# ccnor_stm32_v22-sync.net
KiCad netlist of a schematic drawn in EAGLE
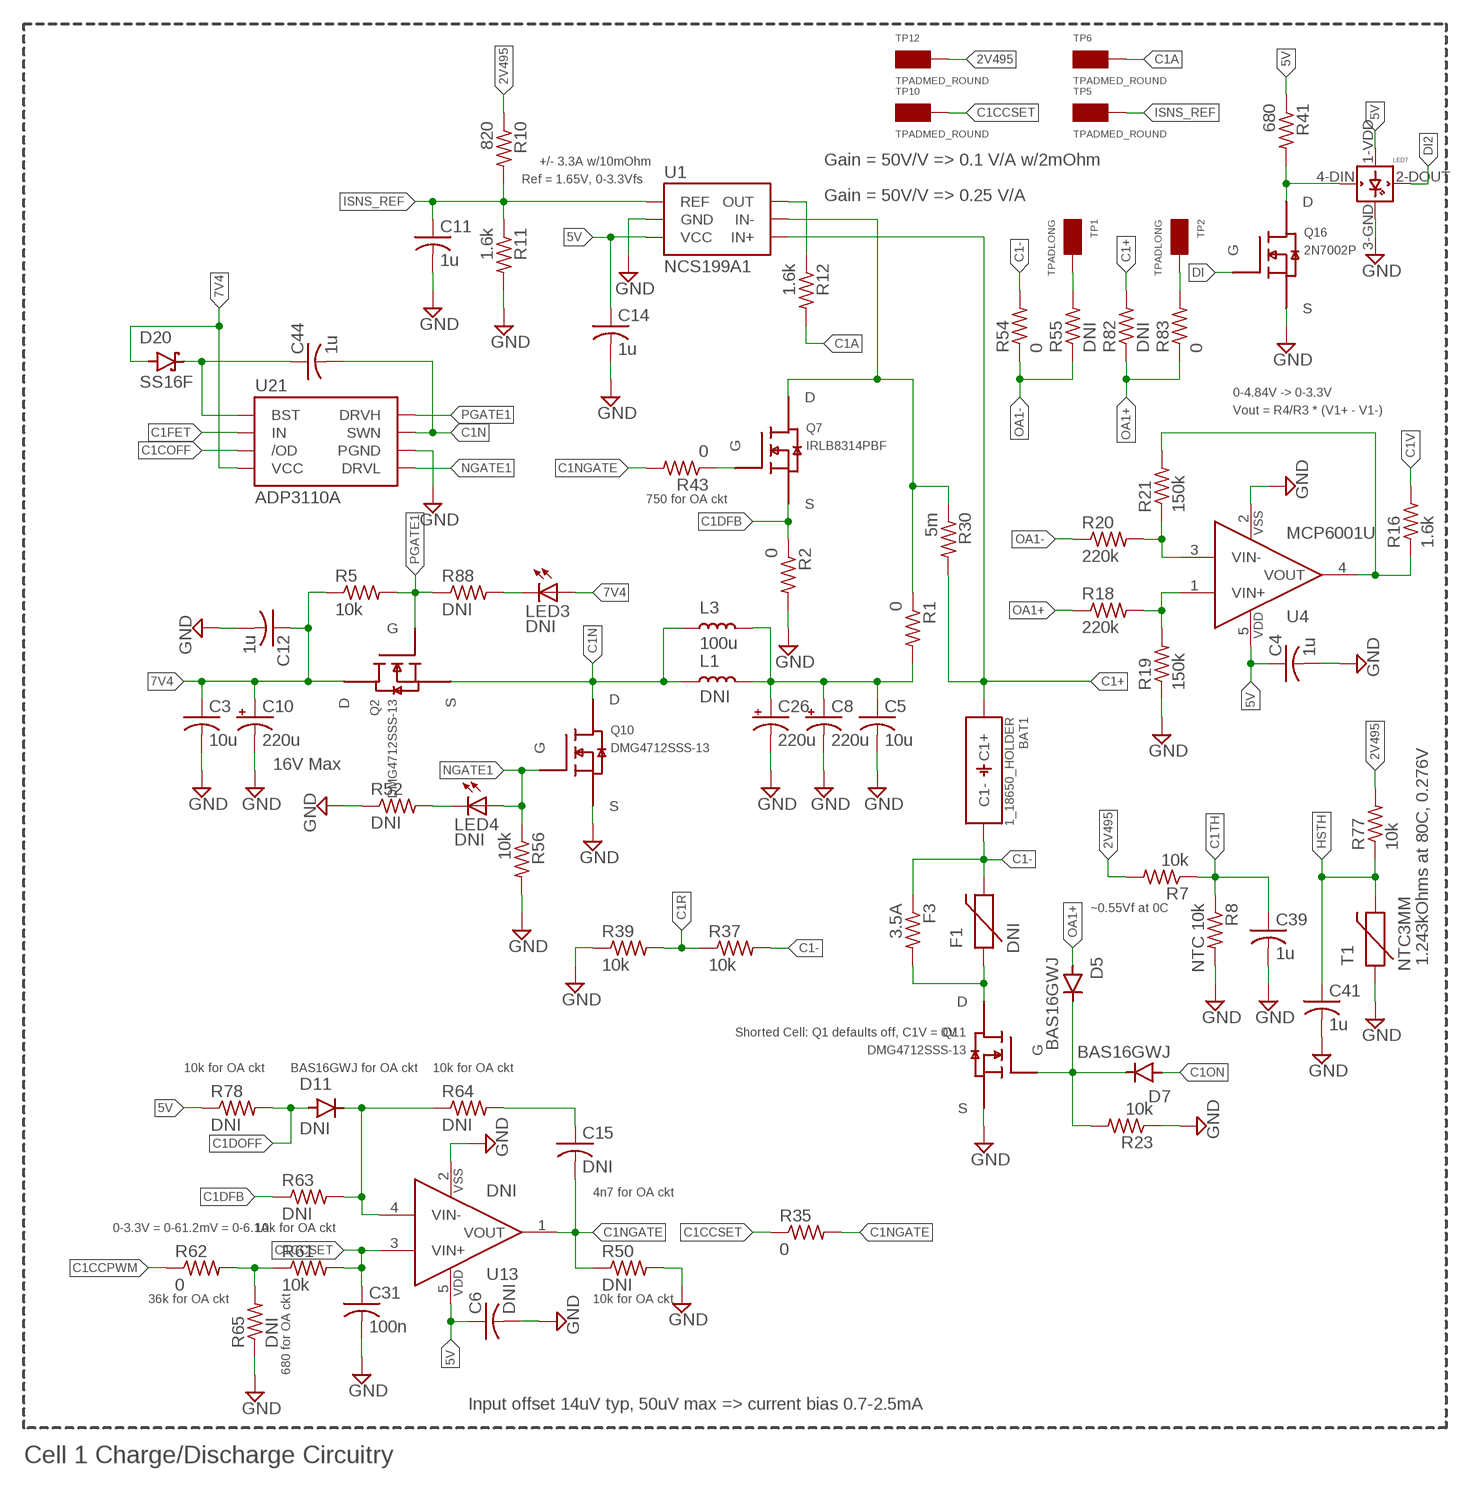
[diagram p0: schematic, sheet 1, part 1 of 2]
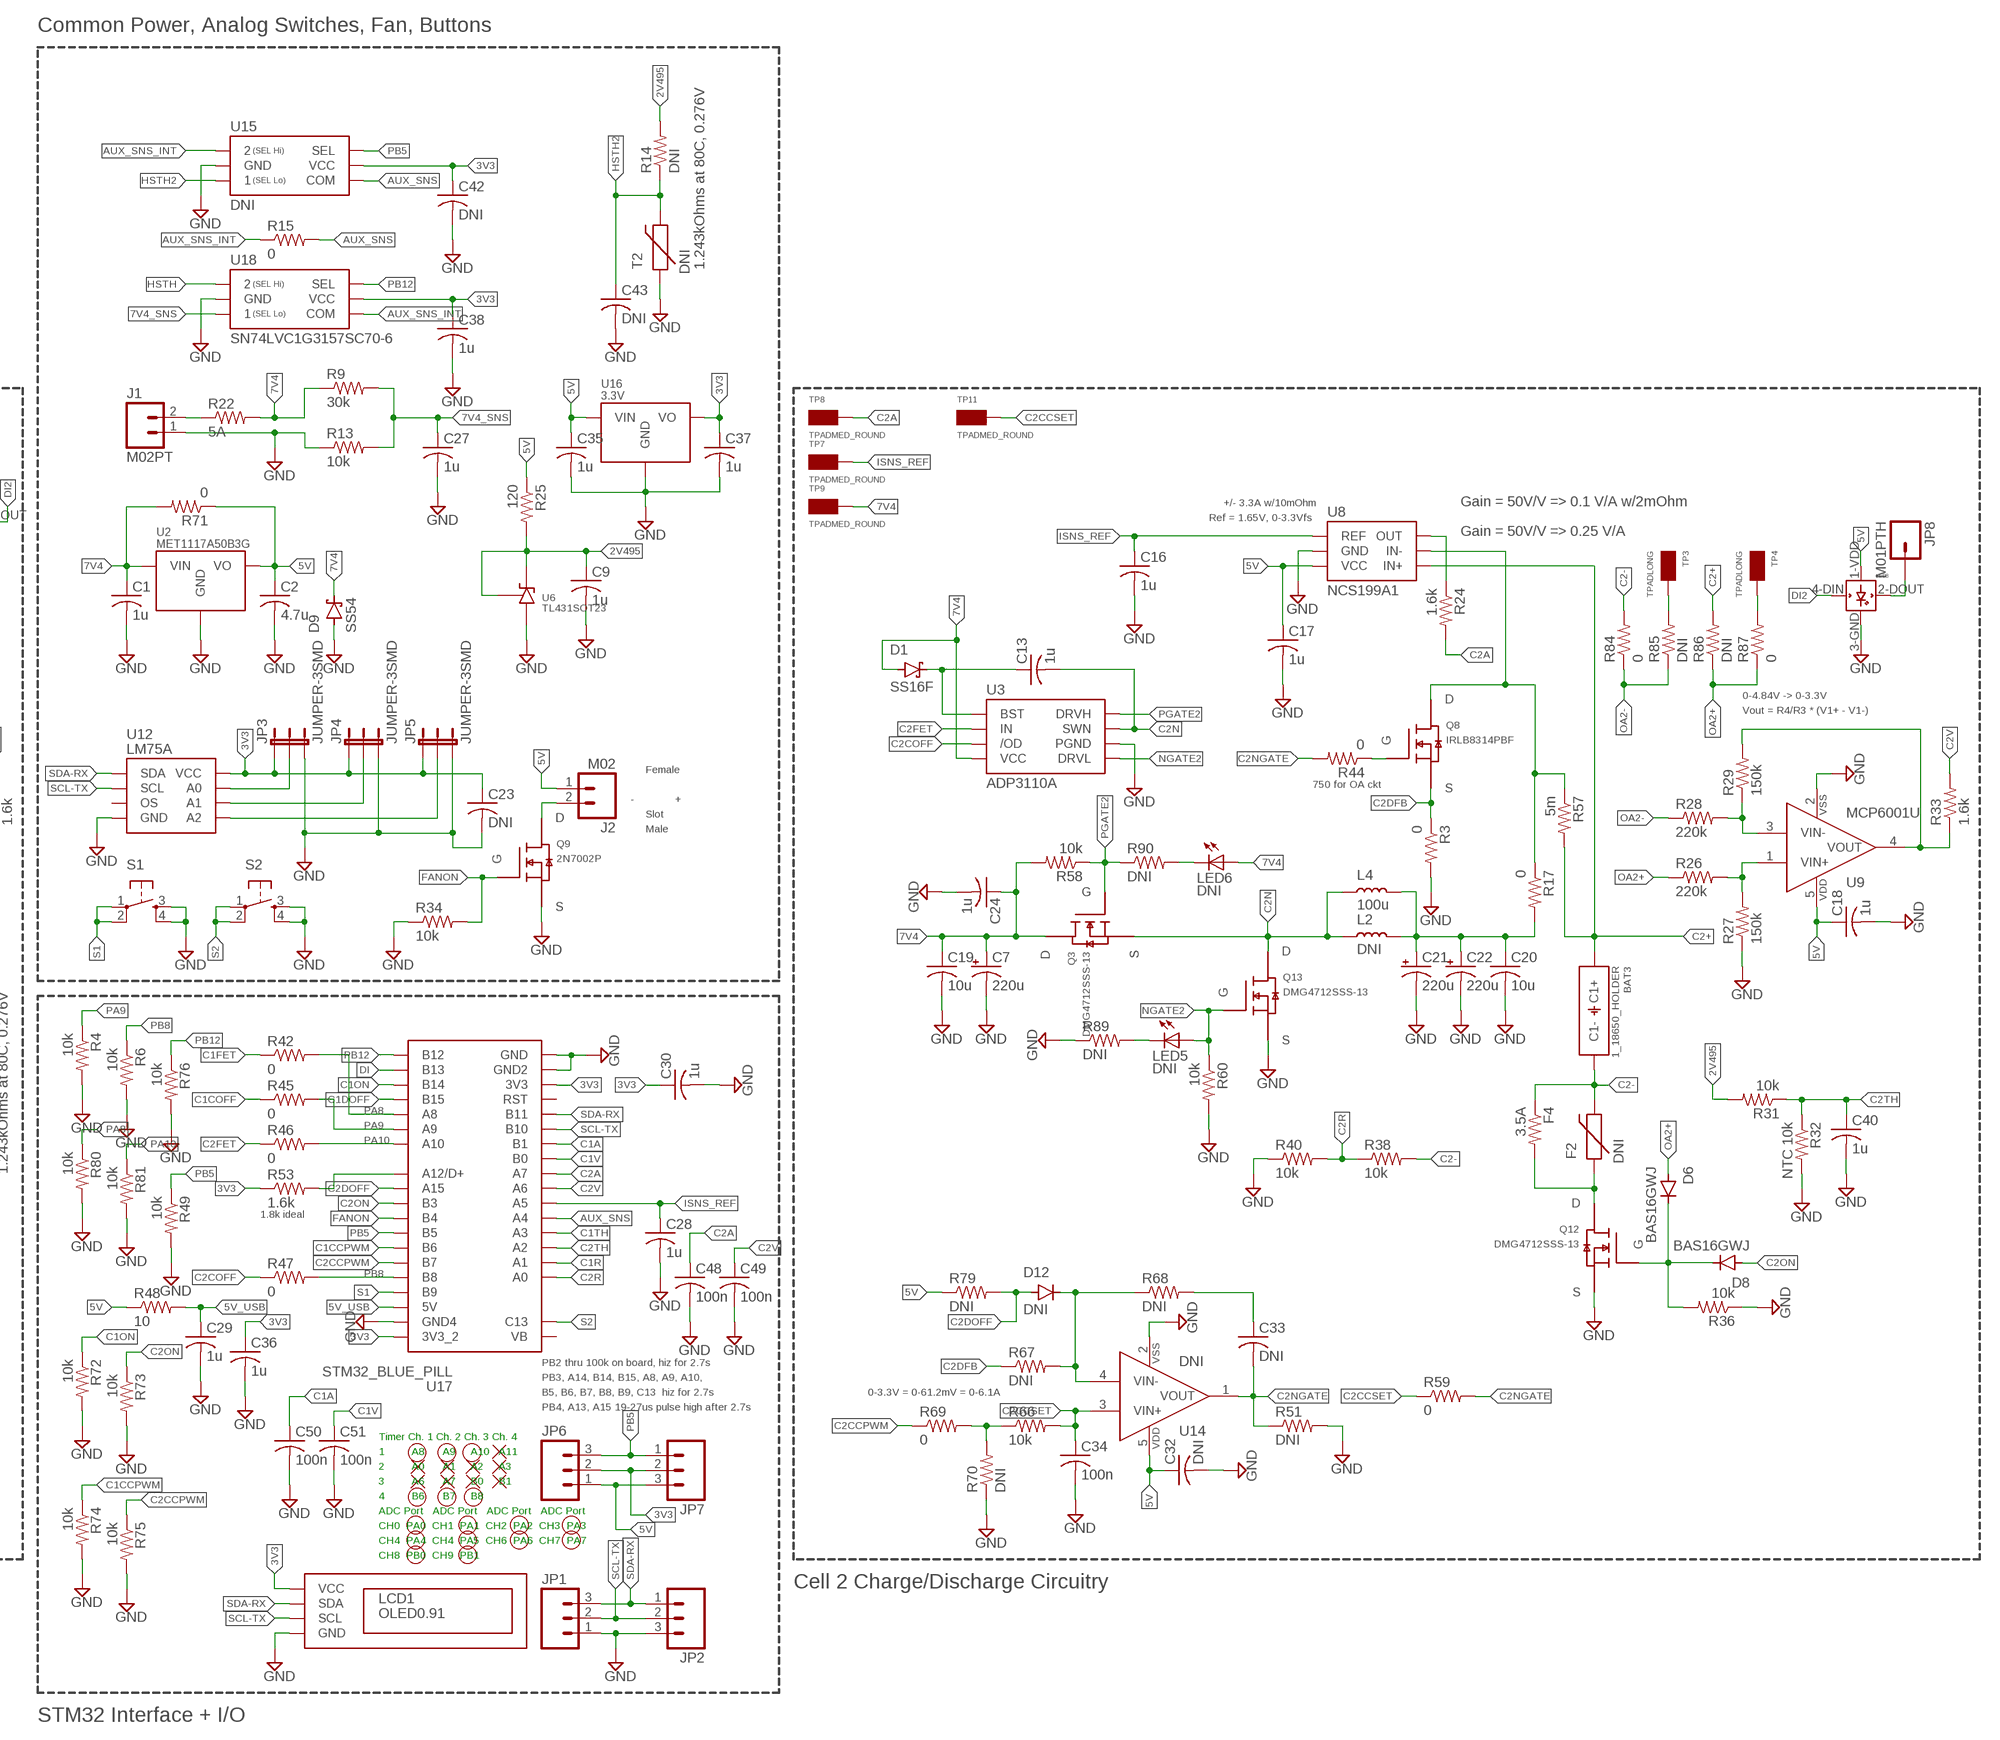
[diagram p1: schematic, sheet 1, part 2 of 2]

(export (version "E")
  (design (tool "Eeschema 10.0.6"))
  (components
    (comp (ref "BAT1")
      (value "1_18650_HOLDER")
      (footprint "eagle-import:1S_18650_SMD_NH")
      (libsource (lib "eagle-import") (part "1_18650_HOLDER"))
    )
    (comp (ref "BAT3")
      (value "1_18650_HOLDER")
      (footprint "eagle-import:1S_18650_SMD_NH")
      (libsource (lib "eagle-import") (part "1_18650_HOLDER"))
    )
    (comp (ref "C1")
      (value "1u")
      (footprint "eagle-import:C0402")
      (libsource (lib "eagle-import") (part "C-USC0402"))
    )
    (comp (ref "C2")
      (value "4.7u")
      (footprint "eagle-import:C0402")
      (libsource (lib "eagle-import") (part "C-USC0402"))
    )
    (comp (ref "C3")
      (value "10u")
      (footprint "eagle-import:C1206")
      (libsource (lib "eagle-import") (part "C-USC1206"))
    )
    (comp (ref "C4")
      (value "1u")
      (footprint "eagle-import:C0402")
      (libsource (lib "eagle-import") (part "C-USC0402"))
    )
    (comp (ref "C5")
      (value "10u")
      (footprint "eagle-import:C1206")
      (libsource (lib "eagle-import") (part "C-USC1206"))
    )
    (comp (ref "C6")
      (value "DNI")
      (footprint "eagle-import:C0402")
      (libsource (lib "eagle-import") (part "C-USC0402"))
    )
    (comp (ref "C7")
      (value "220u")
      (footprint "eagle-import:PANASONIC_D")
      (libsource (lib "eagle-import") (part "CPOL-USD"))
    )
    (comp (ref "C8")
      (value "220u")
      (footprint "eagle-import:PANASONIC_D")
      (libsource (lib "eagle-import") (part "CPOL-USD"))
    )
    (comp (ref "C9")
      (value "1u")
      (footprint "eagle-import:C0402")
      (libsource (lib "eagle-import") (part "C-USC0402"))
    )
    (comp (ref "C10")
      (value "220u")
      (footprint "eagle-import:PANASONIC_D")
      (libsource (lib "eagle-import") (part "CPOL-USD"))
    )
    (comp (ref "C11")
      (value "1u")
      (footprint "eagle-import:C0402")
      (libsource (lib "eagle-import") (part "C-USC0402"))
    )
    (comp (ref "C12")
      (value "1u")
      (footprint "eagle-import:C0402")
      (libsource (lib "eagle-import") (part "C-USC0402"))
    )
    (comp (ref "C13")
      (value "1u")
      (footprint "eagle-import:C0603")
      (libsource (lib "eagle-import") (part "C-USC0603"))
    )
    (comp (ref "C14")
      (value "1u")
      (footprint "eagle-import:C0402")
      (libsource (lib "eagle-import") (part "C-USC0402"))
    )
    (comp (ref "C15")
      (value "DNI")
      (footprint "eagle-import:C0402")
      (libsource (lib "eagle-import") (part "C-USC0402"))
    )
    (comp (ref "C16")
      (value "1u")
      (footprint "eagle-import:C0402")
      (libsource (lib "eagle-import") (part "C-USC0402"))
    )
    (comp (ref "C17")
      (value "1u")
      (footprint "eagle-import:C0402")
      (libsource (lib "eagle-import") (part "C-USC0402"))
    )
    (comp (ref "C18")
      (value "1u")
      (footprint "eagle-import:C0402")
      (libsource (lib "eagle-import") (part "C-USC0402"))
    )
    (comp (ref "C19")
      (value "10u")
      (footprint "eagle-import:C1206")
      (libsource (lib "eagle-import") (part "C-USC1206"))
    )
    (comp (ref "C20")
      (value "10u")
      (footprint "eagle-import:C1206")
      (libsource (lib "eagle-import") (part "C-USC1206"))
    )
    (comp (ref "C21")
      (value "220u")
      (footprint "eagle-import:PANASONIC_D")
      (libsource (lib "eagle-import") (part "CPOL-USD"))
    )
    (comp (ref "C22")
      (value "220u")
      (footprint "eagle-import:PANASONIC_D")
      (libsource (lib "eagle-import") (part "CPOL-USD"))
    )
    (comp (ref "C23")
      (value "DNI")
      (footprint "eagle-import:C0402")
      (libsource (lib "eagle-import") (part "C-USC0402"))
    )
    (comp (ref "C24")
      (value "1u")
      (footprint "eagle-import:C0402")
      (libsource (lib "eagle-import") (part "C-USC0402"))
    )
    (comp (ref "C26")
      (value "220u")
      (footprint "eagle-import:PANASONIC_D")
      (libsource (lib "eagle-import") (part "CPOL-USD"))
    )
    (comp (ref "C27")
      (value "1u")
      (footprint "eagle-import:C0402")
      (libsource (lib "eagle-import") (part "C-USC0402"))
    )
    (comp (ref "C28")
      (value "1u")
      (footprint "eagle-import:C0402")
      (libsource (lib "eagle-import") (part "C-USC0402"))
    )
    (comp (ref "C29")
      (value "1u")
      (footprint "eagle-import:C0402")
      (libsource (lib "eagle-import") (part "C-USC0402"))
    )
    (comp (ref "C30")
      (value "1u")
      (footprint "eagle-import:C0402")
      (libsource (lib "eagle-import") (part "C-USC0402"))
    )
    (comp (ref "C31")
      (value "100n")
      (footprint "eagle-import:C0402")
      (libsource (lib "eagle-import") (part "C-USC0402"))
    )
    (comp (ref "C32")
      (value "DNI")
      (footprint "eagle-import:C0402")
      (libsource (lib "eagle-import") (part "C-USC0402"))
    )
    (comp (ref "C33")
      (value "DNI")
      (footprint "eagle-import:C0402")
      (libsource (lib "eagle-import") (part "C-USC0402"))
    )
    (comp (ref "C34")
      (value "100n")
      (footprint "eagle-import:C0402")
      (libsource (lib "eagle-import") (part "C-USC0402"))
    )
    (comp (ref "C35")
      (value "1u")
      (footprint "eagle-import:C0402")
      (libsource (lib "eagle-import") (part "C-USC0402"))
    )
    (comp (ref "C36")
      (value "1u")
      (footprint "eagle-import:C0402")
      (libsource (lib "eagle-import") (part "C-USC0402"))
    )
    (comp (ref "C37")
      (value "1u")
      (footprint "eagle-import:C0402")
      (libsource (lib "eagle-import") (part "C-USC0402"))
    )
    (comp (ref "C38")
      (value "1u")
      (footprint "eagle-import:C0402")
      (libsource (lib "eagle-import") (part "C-USC0402"))
    )
    (comp (ref "C39")
      (value "1u")
      (footprint "eagle-import:C0402")
      (libsource (lib "eagle-import") (part "C-USC0402"))
    )
    (comp (ref "C40")
      (value "1u")
      (footprint "eagle-import:C0402")
      (libsource (lib "eagle-import") (part "C-USC0402"))
    )
    (comp (ref "C41")
      (value "1u")
      (footprint "eagle-import:C0402")
      (libsource (lib "eagle-import") (part "C-USC0402"))
    )
    (comp (ref "C42")
      (value "DNI")
      (footprint "eagle-import:C0402")
      (libsource (lib "eagle-import") (part "C-USC0402"))
    )
    (comp (ref "C43")
      (value "DNI")
      (footprint "eagle-import:C0402")
      (libsource (lib "eagle-import") (part "C-USC0402"))
    )
    (comp (ref "C44")
      (value "1u")
      (footprint "eagle-import:C0603")
      (libsource (lib "eagle-import") (part "C-USC0603"))
    )
    (comp (ref "C48")
      (value "100n")
      (footprint "eagle-import:C0402")
      (libsource (lib "eagle-import") (part "C-USC0402"))
    )
    (comp (ref "C49")
      (value "100n")
      (footprint "eagle-import:C0402")
      (libsource (lib "eagle-import") (part "C-USC0402"))
    )
    (comp (ref "C50")
      (value "100n")
      (footprint "eagle-import:C0402")
      (libsource (lib "eagle-import") (part "C-USC0402"))
    )
    (comp (ref "C51")
      (value "100n")
      (footprint "eagle-import:C0402")
      (libsource (lib "eagle-import") (part "C-USC0402"))
    )
    (comp (ref "D1")
      (value "SS16F")
      (footprint "eagle-import:SOD123")
      (libsource (lib "eagle-import") (part "DIODE_SCHOTTKYCDBM140-G"))
    )
    (comp (ref "D5")
      (value "BAS16GWJ")
      (footprint "eagle-import:SOD323")
      (libsource (lib "eagle-import") (part "BAT60A"))
    )
    (comp (ref "D6")
      (value "BAS16GWJ")
      (footprint "eagle-import:SOD323")
      (libsource (lib "eagle-import") (part "BAT60A"))
    )
    (comp (ref "D7")
      (value "BAS16GWJ")
      (footprint "eagle-import:SOD323")
      (libsource (lib "eagle-import") (part "BAT60A"))
    )
    (comp (ref "D8")
      (value "BAS16GWJ")
      (footprint "eagle-import:SOD323")
      (libsource (lib "eagle-import") (part "BAT60A"))
    )
    (comp (ref "D9")
      (value "SS54")
      (footprint "eagle-import:SMA")
      (libsource (lib "eagle-import") (part "SS54"))
    )
    (comp (ref "D11")
      (value "DNI")
      (footprint "eagle-import:SOD323")
      (libsource (lib "eagle-import") (part "BAT60A"))
    )
    (comp (ref "D12")
      (value "DNI")
      (footprint "eagle-import:SOD323")
      (libsource (lib "eagle-import") (part "BAT60A"))
    )
    (comp (ref "D20")
      (value "SS16F")
      (footprint "eagle-import:SOD123")
      (libsource (lib "eagle-import") (part "DIODE_SCHOTTKYCDBM140-G"))
    )
    (comp (ref "F1")
      (value "DNI")
      (footprint "eagle-import:1812")
      (libsource (lib "eagle-import") (part "PTC1812"))
    )
    (comp (ref "F2")
      (value "DNI")
      (footprint "eagle-import:1812")
      (libsource (lib "eagle-import") (part "PTC1812"))
    )
    (comp (ref "F3")
      (value "3.5A")
      (footprint "eagle-import:R1206")
      (libsource (lib "eagle-import") (part "R-US_R1206"))
    )
    (comp (ref "F4")
      (value "3.5A")
      (footprint "eagle-import:R1206")
      (libsource (lib "eagle-import") (part "R-US_R1206"))
    )
    (comp (ref "J1")
      (value "M02PT")
      (footprint "eagle-import:PHOENIXCONTACT1935161")
      (libsource (lib "eagle-import") (part "M02PT"))
    )
    (comp (ref "J2")
      (value "M02")
      (footprint "eagle-import:B2B-XH-A")
      (libsource (lib "eagle-import") (part "M02"))
    )
    (comp (ref "JP1")
      (value "M03PTH")
      (footprint "eagle-import:1X03")
      (libsource (lib "eagle-import") (part "M03PTH"))
    )
    (comp (ref "JP2")
      (value "M03PTH")
      (footprint "eagle-import:1X03")
      (libsource (lib "eagle-import") (part "M03PTH"))
    )
    (comp (ref "JP3")
      (value "JUMPER-3SMD")
      (footprint "eagle-import:SJ_3")
      (libsource (lib "eagle-import") (part "JUMPER-3SMD"))
    )
    (comp (ref "JP4")
      (value "JUMPER-3SMD")
      (footprint "eagle-import:SJ_3")
      (libsource (lib "eagle-import") (part "JUMPER-3SMD"))
    )
    (comp (ref "JP5")
      (value "JUMPER-3SMD")
      (footprint "eagle-import:SJ_3")
      (libsource (lib "eagle-import") (part "JUMPER-3SMD"))
    )
    (comp (ref "JP6")
      (value "M03PTH")
      (footprint "eagle-import:1X03")
      (libsource (lib "eagle-import") (part "M03PTH"))
    )
    (comp (ref "JP7")
      (value "M03PTH")
      (footprint "eagle-import:1X03")
      (libsource (lib "eagle-import") (part "M03PTH"))
    )
    (comp (ref "JP8")
      (value "M01PTH")
      (footprint "eagle-import:1X01")
      (libsource (lib "eagle-import") (part "M01PTH"))
    )
    (comp (ref "L1")
      (value "DNI")
      (footprint "eagle-import:INDUCTOR_SMD_13MM")
      (libsource (lib "eagle-import") (part "SDR1307"))
    )
    (comp (ref "L2")
      (value "DNI")
      (footprint "eagle-import:INDUCTOR_SMD_13MM")
      (libsource (lib "eagle-import") (part "SDR1307"))
    )
    (comp (ref "L3")
      (value "100u")
      (footprint "eagle-import:INDUCTOR_6A_8MMX15MM")
      (libsource (lib "eagle-import") (part "INDUCTOR6A-LG"))
    )
    (comp (ref "L4")
      (value "100u")
      (footprint "eagle-import:INDUCTOR_6A_8MMX15MM")
      (libsource (lib "eagle-import") (part "INDUCTOR6A-LG"))
    )
    (comp (ref "LCD1")
      (value "OLED0.91")
      (footprint "eagle-import:OLED0.91")
      (libsource (lib "eagle-import") (part "OLED0.91"))
    )
    (comp (ref "LED3")
      (value "DNI")
      (footprint "eagle-import:CHIPLED_0603")
      (libsource (lib "eagle-import") (part "LEDCHIPLED_0603"))
    )
    (comp (ref "LED4")
      (value "DNI")
      (footprint "eagle-import:CHIPLED_0603")
      (libsource (lib "eagle-import") (part "LEDCHIPLED_0603"))
    )
    (comp (ref "LED5")
      (value "DNI")
      (footprint "eagle-import:CHIPLED_0603")
      (libsource (lib "eagle-import") (part "LEDCHIPLED_0603"))
    )
    (comp (ref "LED6")
      (value "DNI")
      (footprint "eagle-import:CHIPLED_0603")
      (libsource (lib "eagle-import") (part "LEDCHIPLED_0603"))
    )
    (comp (ref "LED7")
      (value "WS2812B")
      (footprint "eagle-import:WS2812B")
      (libsource (lib "eagle-import") (part "WS2812B"))
    )
    (comp (ref "LED8")
      (value "WS2812B")
      (footprint "eagle-import:WS2812B")
      (libsource (lib "eagle-import") (part "WS2812B"))
    )
    (comp (ref "Q2")
      (value "DMG4712SSS-13")
      (footprint "eagle-import:8-SOIC")
      (libsource (lib "eagle-import") (part "N-MOSFET-SOIC8"))
    )
    (comp (ref "Q3")
      (value "DMG4712SSS-13")
      (footprint "eagle-import:8-SOIC")
      (libsource (lib "eagle-import") (part "N-MOSFET-SOIC8"))
    )
    (comp (ref "Q7")
      (value "IRLB8314PBF")
      (footprint "eagle-import:TO-220")
      (libsource (lib "eagle-import") (part "IRLB8314PBF"))
    )
    (comp (ref "Q8")
      (value "IRLB8314PBF")
      (footprint "eagle-import:TO-220")
      (libsource (lib "eagle-import") (part "IRLB8314PBF"))
    )
    (comp (ref "Q9")
      (value "2N7002P")
      (footprint "eagle-import:SOT23")
      (libsource (lib "eagle-import") (part "2N7002P"))
    )
    (comp (ref "Q10")
      (value "DMG4712SSS-13")
      (footprint "eagle-import:8-SOIC")
      (libsource (lib "eagle-import") (part "N-MOSFET-SOIC8"))
    )
    (comp (ref "Q11")
      (value "DMG4712SSS-13")
      (footprint "eagle-import:8-SOIC")
      (libsource (lib "eagle-import") (part "N-MOSFET-SOIC8"))
    )
    (comp (ref "Q12")
      (value "DMG4712SSS-13")
      (footprint "eagle-import:8-SOIC")
      (libsource (lib "eagle-import") (part "N-MOSFET-SOIC8"))
    )
    (comp (ref "Q13")
      (value "DMG4712SSS-13")
      (footprint "eagle-import:8-SOIC")
      (libsource (lib "eagle-import") (part "N-MOSFET-SOIC8"))
    )
    (comp (ref "Q16")
      (value "2N7002P")
      (footprint "eagle-import:SOT23")
      (libsource (lib "eagle-import") (part "2N7002P"))
    )
    (comp (ref "R1")
      (value "0")
      (footprint "eagle-import:R1206")
      (libsource (lib "eagle-import") (part "R-US_R1206"))
    )
    (comp (ref "R2")
      (value "0")
      (footprint "eagle-import:R1206")
      (libsource (lib "eagle-import") (part "R-US_R1206"))
    )
    (comp (ref "R3")
      (value "0")
      (footprint "eagle-import:R1206")
      (libsource (lib "eagle-import") (part "R-US_R1206"))
    )
    (comp (ref "R4")
      (value "10k")
      (footprint "eagle-import:R0402")
      (libsource (lib "eagle-import") (part "R-US_R0402"))
    )
    (comp (ref "R5")
      (value "10k")
      (footprint "eagle-import:R0402")
      (libsource (lib "eagle-import") (part "R-US_R0402"))
    )
    (comp (ref "R6")
      (value "10k")
      (footprint "eagle-import:R0402")
      (libsource (lib "eagle-import") (part "R-US_R0402"))
    )
    (comp (ref "R7")
      (value "10k")
      (footprint "eagle-import:R0402")
      (libsource (lib "eagle-import") (part "R-US_R0402"))
    )
    (comp (ref "R8")
      (value "NTC 10k")
      (footprint "eagle-import:R0402")
      (libsource (lib "eagle-import") (part "R-US_R0402"))
    )
    (comp (ref "R9")
      (value "30k")
      (footprint "eagle-import:R0402")
      (libsource (lib "eagle-import") (part "R-US_R0402"))
    )
    (comp (ref "R10")
      (value "820")
      (footprint "eagle-import:R0402")
      (libsource (lib "eagle-import") (part "R-US_R0402"))
    )
    (comp (ref "R11")
      (value "1.6k")
      (footprint "eagle-import:R0402")
      (libsource (lib "eagle-import") (part "R-US_R0402"))
    )
    (comp (ref "R12")
      (value "1.6k")
      (footprint "eagle-import:R0402")
      (libsource (lib "eagle-import") (part "R-US_R0402"))
    )
    (comp (ref "R13")
      (value "10k")
      (footprint "eagle-import:R0402")
      (libsource (lib "eagle-import") (part "R-US_R0402"))
    )
    (comp (ref "R14")
      (value "DNI")
      (footprint "eagle-import:R0402")
      (libsource (lib "eagle-import") (part "R-US_R0402"))
    )
    (comp (ref "R15")
      (value "0")
      (footprint "eagle-import:R0402")
      (libsource (lib "eagle-import") (part "R-US_R0402"))
    )
    (comp (ref "R16")
      (value "1.6k")
      (footprint "eagle-import:R0402")
      (libsource (lib "eagle-import") (part "R-US_R0402"))
    )
    (comp (ref "R17")
      (value "0")
      (footprint "eagle-import:R1206")
      (libsource (lib "eagle-import") (part "R-US_R1206"))
    )
    (comp (ref "R18")
      (value "220k")
      (footprint "eagle-import:R0402")
      (libsource (lib "eagle-import") (part "R-US_R0402"))
    )
    (comp (ref "R19")
      (value "150k")
      (footprint "eagle-import:R0402")
      (libsource (lib "eagle-import") (part "R-US_R0402"))
    )
    (comp (ref "R20")
      (value "220k")
      (footprint "eagle-import:R0402")
      (libsource (lib "eagle-import") (part "R-US_R0402"))
    )
    (comp (ref "R21")
      (value "150k")
      (footprint "eagle-import:R0402")
      (libsource (lib "eagle-import") (part "R-US_R0402"))
    )
    (comp (ref "R22")
      (value "5A")
      (footprint "eagle-import:R1206")
      (libsource (lib "eagle-import") (part "R-US_R1206"))
    )
    (comp (ref "R23")
      (value "10k")
      (footprint "eagle-import:R0402")
      (libsource (lib "eagle-import") (part "R-US_R0402"))
    )
    (comp (ref "R24")
      (value "1.6k")
      (footprint "eagle-import:R0402")
      (libsource (lib "eagle-import") (part "R-US_R0402"))
    )
    (comp (ref "R25")
      (value "120")
      (footprint "eagle-import:R0402")
      (libsource (lib "eagle-import") (part "R-US_R0402"))
    )
    (comp (ref "R26")
      (value "220k")
      (footprint "eagle-import:R0402")
      (libsource (lib "eagle-import") (part "R-US_R0402"))
    )
    (comp (ref "R27")
      (value "150k")
      (footprint "eagle-import:R0402")
      (libsource (lib "eagle-import") (part "R-US_R0402"))
    )
    (comp (ref "R28")
      (value "220k")
      (footprint "eagle-import:R0402")
      (libsource (lib "eagle-import") (part "R-US_R0402"))
    )
    (comp (ref "R29")
      (value "150k")
      (footprint "eagle-import:R0402")
      (libsource (lib "eagle-import") (part "R-US_R0402"))
    )
    (comp (ref "R30")
      (value "5m")
      (footprint "eagle-import:R1206")
      (libsource (lib "eagle-import") (part "R-US_R1206"))
    )
    (comp (ref "R31")
      (value "10k")
      (footprint "eagle-import:R0402")
      (libsource (lib "eagle-import") (part "R-US_R0402"))
    )
    (comp (ref "R32")
      (value "NTC 10k")
      (footprint "eagle-import:R0402")
      (libsource (lib "eagle-import") (part "R-US_R0402"))
    )
    (comp (ref "R33")
      (value "1.6k")
      (footprint "eagle-import:R0402")
      (libsource (lib "eagle-import") (part "R-US_R0402"))
    )
    (comp (ref "R34")
      (value "10k")
      (footprint "eagle-import:R0402")
      (libsource (lib "eagle-import") (part "R-US_R0402"))
    )
    (comp (ref "R35")
      (value "0")
      (footprint "eagle-import:R0402")
      (libsource (lib "eagle-import") (part "R-US_R0402"))
    )
    (comp (ref "R36")
      (value "10k")
      (footprint "eagle-import:R0402")
      (libsource (lib "eagle-import") (part "R-US_R0402"))
    )
    (comp (ref "R37")
      (value "10k")
      (footprint "eagle-import:R0402")
      (libsource (lib "eagle-import") (part "R-US_R0402"))
    )
    (comp (ref "R38")
      (value "10k")
      (footprint "eagle-import:R0402")
      (libsource (lib "eagle-import") (part "R-US_R0402"))
    )
    (comp (ref "R39")
      (value "10k")
      (footprint "eagle-import:R0402")
      (libsource (lib "eagle-import") (part "R-US_R0402"))
    )
    (comp (ref "R40")
      (value "10k")
      (footprint "eagle-import:R0402")
      (libsource (lib "eagle-import") (part "R-US_R0402"))
    )
    (comp (ref "R41")
      (value "680")
      (footprint "eagle-import:R0402")
      (libsource (lib "eagle-import") (part "R-US_R0402"))
    )
    (comp (ref "R42")
      (value "0")
      (footprint "eagle-import:R0402")
      (libsource (lib "eagle-import") (part "R-US_R0402"))
    )
    (comp (ref "R43")
      (value "0")
      (footprint "eagle-import:R0402")
      (libsource (lib "eagle-import") (part "R-US_R0402"))
    )
    (comp (ref "R44")
      (value "0")
      (footprint "eagle-import:R0402")
      (libsource (lib "eagle-import") (part "R-US_R0402"))
    )
    (comp (ref "R45")
      (value "0")
      (footprint "eagle-import:R0402")
      (libsource (lib "eagle-import") (part "R-US_R0402"))
    )
    (comp (ref "R46")
      (value "0")
      (footprint "eagle-import:R0402")
      (libsource (lib "eagle-import") (part "R-US_R0402"))
    )
    (comp (ref "R47")
      (value "0")
      (footprint "eagle-import:R0402")
      (libsource (lib "eagle-import") (part "R-US_R0402"))
    )
    (comp (ref "R48")
      (value "10")
      (footprint "eagle-import:R0402")
      (libsource (lib "eagle-import") (part "R-US_R0402"))
    )
    (comp (ref "R49")
      (value "10k")
      (footprint "eagle-import:R0402")
      (libsource (lib "eagle-import") (part "R-US_R0402"))
    )
    (comp (ref "R50")
      (value "DNI")
      (footprint "eagle-import:R0402")
      (libsource (lib "eagle-import") (part "R-US_R0402"))
    )
    (comp (ref "R51")
      (value "DNI")
      (footprint "eagle-import:R0402")
      (libsource (lib "eagle-import") (part "R-US_R0402"))
    )
    (comp (ref "R52")
      (value "DNI")
      (footprint "eagle-import:R0402")
      (libsource (lib "eagle-import") (part "R-US_R0402"))
    )
    (comp (ref "R53")
      (value "1.6k")
      (footprint "eagle-import:R0402")
      (libsource (lib "eagle-import") (part "R-US_R0402"))
    )
    (comp (ref "R54")
      (value "0")
      (footprint "eagle-import:R0402")
      (libsource (lib "eagle-import") (part "R-US_R0402"))
    )
    (comp (ref "R55")
      (value "DNI")
      (footprint "eagle-import:R0402")
      (libsource (lib "eagle-import") (part "R-US_R0402"))
    )
    (comp (ref "R56")
      (value "10k")
      (footprint "eagle-import:R0402")
      (libsource (lib "eagle-import") (part "R-US_R0402"))
    )
    (comp (ref "R57")
      (value "5m")
      (footprint "eagle-import:R1206")
      (libsource (lib "eagle-import") (part "R-US_R1206"))
    )
    (comp (ref "R58")
      (value "10k")
      (footprint "eagle-import:R0402")
      (libsource (lib "eagle-import") (part "R-US_R0402"))
    )
    (comp (ref "R59")
      (value "0")
      (footprint "eagle-import:R0402")
      (libsource (lib "eagle-import") (part "R-US_R0402"))
    )
    (comp (ref "R60")
      (value "10k")
      (footprint "eagle-import:R0402")
      (libsource (lib "eagle-import") (part "R-US_R0402"))
    )
    (comp (ref "R61")
      (value "10k")
      (footprint "eagle-import:R0402")
      (libsource (lib "eagle-import") (part "R-US_R0402"))
    )
    (comp (ref "R62")
      (value "0")
      (footprint "eagle-import:R0402")
      (libsource (lib "eagle-import") (part "R-US_R0402"))
    )
    (comp (ref "R63")
      (value "DNI")
      (footprint "eagle-import:R0402")
      (libsource (lib "eagle-import") (part "R-US_R0402"))
    )
    (comp (ref "R64")
      (value "DNI")
      (footprint "eagle-import:R0402")
      (libsource (lib "eagle-import") (part "R-US_R0402"))
    )
    (comp (ref "R65")
      (value "DNI")
      (footprint "eagle-import:R0402")
      (libsource (lib "eagle-import") (part "R-US_R0402"))
    )
    (comp (ref "R66")
      (value "10k")
      (footprint "eagle-import:R0402")
      (libsource (lib "eagle-import") (part "R-US_R0402"))
    )
    (comp (ref "R67")
      (value "DNI")
      (footprint "eagle-import:R0402")
      (libsource (lib "eagle-import") (part "R-US_R0402"))
    )
    (comp (ref "R68")
      (value "DNI")
      (footprint "eagle-import:R0402")
      (libsource (lib "eagle-import") (part "R-US_R0402"))
    )
    (comp (ref "R69")
      (value "0")
      (footprint "eagle-import:R0402")
      (libsource (lib "eagle-import") (part "R-US_R0402"))
    )
    (comp (ref "R70")
      (value "DNI")
      (footprint "eagle-import:R0402")
      (libsource (lib "eagle-import") (part "R-US_R0402"))
    )
    (comp (ref "R71")
      (value "0")
      (footprint "eagle-import:R0603")
      (libsource (lib "eagle-import") (part "R-US_R0603"))
    )
    (comp (ref "R72")
      (value "10k")
      (footprint "eagle-import:R0402")
      (libsource (lib "eagle-import") (part "R-US_R0402"))
    )
    (comp (ref "R73")
      (value "10k")
      (footprint "eagle-import:R0402")
      (libsource (lib "eagle-import") (part "R-US_R0402"))
    )
    (comp (ref "R74")
      (value "10k")
      (footprint "eagle-import:R0402")
      (libsource (lib "eagle-import") (part "R-US_R0402"))
    )
    (comp (ref "R75")
      (value "10k")
      (footprint "eagle-import:R0402")
      (libsource (lib "eagle-import") (part "R-US_R0402"))
    )
    (comp (ref "R76")
      (value "10k")
      (footprint "eagle-import:R0402")
      (libsource (lib "eagle-import") (part "R-US_R0402"))
    )
    (comp (ref "R77")
      (value "10k")
      (footprint "eagle-import:R0402")
      (libsource (lib "eagle-import") (part "R-US_R0402"))
    )
    (comp (ref "R78")
      (value "DNI")
      (footprint "eagle-import:R0402")
      (libsource (lib "eagle-import") (part "R-US_R0402"))
    )
    (comp (ref "R79")
      (value "DNI")
      (footprint "eagle-import:R0402")
      (libsource (lib "eagle-import") (part "R-US_R0402"))
    )
    (comp (ref "R80")
      (value "10k")
      (footprint "eagle-import:R0402")
      (libsource (lib "eagle-import") (part "R-US_R0402"))
    )
    (comp (ref "R81")
      (value "10k")
      (footprint "eagle-import:R0402")
      (libsource (lib "eagle-import") (part "R-US_R0402"))
    )
    (comp (ref "R82")
      (value "DNI")
      (footprint "eagle-import:R0402")
      (libsource (lib "eagle-import") (part "R-US_R0402"))
    )
    (comp (ref "R83")
      (value "0")
      (footprint "eagle-import:R0402")
      (libsource (lib "eagle-import") (part "R-US_R0402"))
    )
    (comp (ref "R84")
      (value "0")
      (footprint "eagle-import:R0402")
      (libsource (lib "eagle-import") (part "R-US_R0402"))
    )
    (comp (ref "R85")
      (value "DNI")
      (footprint "eagle-import:R0402")
      (libsource (lib "eagle-import") (part "R-US_R0402"))
    )
    (comp (ref "R86")
      (value "DNI")
      (footprint "eagle-import:R0402")
      (libsource (lib "eagle-import") (part "R-US_R0402"))
    )
    (comp (ref "R87")
      (value "0")
      (footprint "eagle-import:R0402")
      (libsource (lib "eagle-import") (part "R-US_R0402"))
    )
    (comp (ref "R88")
      (value "DNI")
      (footprint "eagle-import:R0402")
      (libsource (lib "eagle-import") (part "R-US_R0402"))
    )
    (comp (ref "R89")
      (value "DNI")
      (footprint "eagle-import:R0402")
      (libsource (lib "eagle-import") (part "R-US_R0402"))
    )
    (comp (ref "R90")
      (value "DNI")
      (footprint "eagle-import:R0402")
      (libsource (lib "eagle-import") (part "R-US_R0402"))
    )
    (comp (ref "S1")
      (value "TAC_SWITCHSMD")
      (footprint "eagle-import:TACTILE_SWITCH_SMD")
      (libsource (lib "eagle-import") (part "TAC_SWITCHSMD"))
    )
    (comp (ref "S2")
      (value "TAC_SWITCHSMD")
      (footprint "eagle-import:TACTILE_SWITCH_SMD")
      (libsource (lib "eagle-import") (part "TAC_SWITCHSMD"))
    )
    (comp (ref "T1")
      (value "NTC3MM")
      (footprint "eagle-import:THERMISTOR_3MMX3MM")
      (libsource (lib "eagle-import") (part "PTCNTC3MM"))
    )
    (comp (ref "T2")
      (value "DNI")
      (footprint "eagle-import:THERMISTOR_3MMX3MM")
      (libsource (lib "eagle-import") (part "PTCNTC3MM"))
    )
    (comp (ref "TP1")
      (value "TPADLONG")
      (footprint "eagle-import:TPAD_LONG")
      (libsource (lib "eagle-import") (part "TPADLONG"))
    )
    (comp (ref "TP2")
      (value "TPADLONG")
      (footprint "eagle-import:TPAD_LONG")
      (libsource (lib "eagle-import") (part "TPADLONG"))
    )
    (comp (ref "TP3")
      (value "TPADLONG")
      (footprint "eagle-import:TPAD_LONG")
      (libsource (lib "eagle-import") (part "TPADLONG"))
    )
    (comp (ref "TP4")
      (value "TPADLONG")
      (footprint "eagle-import:TPAD_LONG")
      (libsource (lib "eagle-import") (part "TPADLONG"))
    )
    (comp (ref "TP5")
      (value "TPADMED_ROUND")
      (footprint "eagle-import:TPAD_MED_ROUND")
      (libsource (lib "eagle-import") (part "TPADMED_ROUND"))
    )
    (comp (ref "TP6")
      (value "TPADMED_ROUND")
      (footprint "eagle-import:TPAD_MED_ROUND")
      (libsource (lib "eagle-import") (part "TPADMED_ROUND"))
    )
    (comp (ref "TP7")
      (value "TPADMED_ROUND")
      (footprint "eagle-import:TPAD_MED_ROUND")
      (libsource (lib "eagle-import") (part "TPADMED_ROUND"))
    )
    (comp (ref "TP8")
      (value "TPADMED_ROUND")
      (footprint "eagle-import:TPAD_MED_ROUND")
      (libsource (lib "eagle-import") (part "TPADMED_ROUND"))
    )
    (comp (ref "TP9")
      (value "TPADMED_ROUND")
      (footprint "eagle-import:TPAD_MED_ROUND")
      (libsource (lib "eagle-import") (part "TPADMED_ROUND"))
    )
    (comp (ref "TP10")
      (value "TPADMED_ROUND")
      (footprint "eagle-import:TPAD_MED_ROUND")
      (libsource (lib "eagle-import") (part "TPADMED_ROUND"))
    )
    (comp (ref "TP11")
      (value "TPADMED_ROUND")
      (footprint "eagle-import:TPAD_MED_ROUND")
      (libsource (lib "eagle-import") (part "TPADMED_ROUND"))
    )
    (comp (ref "TP12")
      (value "TPADMED_ROUND")
      (footprint "eagle-import:TPAD_MED_ROUND")
      (libsource (lib "eagle-import") (part "TPADMED_ROUND"))
    )
    (comp (ref "U1")
      (value "NCS199A1")
      (footprint "eagle-import:SOT-363")
      (libsource (lib "eagle-import") (part "INA214"))
    )
    (comp (ref "U2")
      (value "MET1117A50B3G")
      (footprint "eagle-import:TO-261")
      (libsource (lib "eagle-import") (part "ZLDO1117"))
    )
    (comp (ref "U3")
      (value "ADP3110A")
      (footprint "eagle-import:8-SOIC")
      (libsource (lib "eagle-import") (part "ADP3110A"))
    )
    (comp (ref "U4")
      (value "MCP6001U")
      (footprint "eagle-import:SOT23-5")
      (libsource (lib "eagle-import") (part "MCP6001U"))
    )
    (comp (ref "U6")
      (value "TL431SOT23")
      (footprint "eagle-import:SOT23")
      (libsource (lib "eagle-import") (part "TL431SOT23"))
    )
    (comp (ref "U8")
      (value "NCS199A1")
      (footprint "eagle-import:SOT-363")
      (libsource (lib "eagle-import") (part "INA214"))
    )
    (comp (ref "U9")
      (value "MCP6001U")
      (footprint "eagle-import:SOT23-5")
      (libsource (lib "eagle-import") (part "MCP6001U"))
    )
    (comp (ref "U12")
      (value "LM75A")
      (footprint "eagle-import:8-SOIC")
      (libsource (lib "eagle-import") (part "LM75A"))
    )
    (comp (ref "U13")
      (value "DNI")
      (footprint "eagle-import:SOT23-5")
      (libsource (lib "eagle-import") (part "NCS325"))
    )
    (comp (ref "U14")
      (value "DNI")
      (footprint "eagle-import:SOT23-5")
      (libsource (lib "eagle-import") (part "NCS325"))
    )
    (comp (ref "U15")
      (value "DNI")
      (footprint "eagle-import:SC70-6")
      (libsource (lib "eagle-import") (part "SN74LVC1G3157SC70-6"))
    )
    (comp (ref "U16")
      (value "3.3V")
      (footprint "eagle-import:SOT-89")
      (libsource (lib "eagle-import") (part "AP1117UR133-B"))
    )
    (comp (ref "U17")
      (value "STM32_BLUE_PILL")
      (footprint "eagle-import:STM32_BLUE_PILL_USABLE")
      (libsource (lib "eagle-import") (part "STM32_BLUE_PILL"))
    )
    (comp (ref "U18")
      (value "SN74LVC1G3157SC70-6")
      (footprint "eagle-import:SC70-6")
      (libsource (lib "eagle-import") (part "SN74LVC1G3157SC70-6"))
    )
    (comp (ref "U21")
      (value "ADP3110A")
      (footprint "eagle-import:8-SOIC")
      (libsource (lib "eagle-import") (part "ADP3110A"))
    )
  )
  (nets
    (net (code "1") (name "2V495") (class "Default")
      (node (ref "C9") (pin "1") (pinfunction "1_1") (pintype "passive"))
      (node (ref "R10") (pin "1") (pinfunction "1_1") (pintype "passive"))
      (node (ref "R14") (pin "2") (pinfunction "2_2") (pintype "passive"))
      (node (ref "R25") (pin "2") (pinfunction "2_2") (pintype "passive"))
      (node (ref "R31") (pin "2") (pinfunction "2_2") (pintype "passive"))
      (node (ref "R7") (pin "2") (pinfunction "2_2") (pintype "passive"))
      (node (ref "R77") (pin "2") (pinfunction "2_2") (pintype "passive"))
      (node (ref "TP12") (pin "1") (pinfunction "1_1") (pintype "bidirectional"))
      (node (ref "U6") (pin "1") (pinfunction "K_1") (pintype "passive"))
      (node (ref "U6") (pin "2") (pinfunction "REF_2") (pintype "passive"))
    )
    (net (code "2") (name "3V3") (class "Default")
      (node (ref "C23") (pin "1") (pinfunction "1_1") (pintype "passive"))
      (node (ref "C30") (pin "1") (pinfunction "1_1") (pintype "passive"))
      (node (ref "C36") (pin "1") (pinfunction "1_1") (pintype "passive"))
      (node (ref "C37") (pin "1") (pinfunction "1_1") (pintype "passive"))
      (node (ref "C38") (pin "1") (pinfunction "1_1") (pintype "passive"))
      (node (ref "C42") (pin "1") (pinfunction "1_1") (pintype "passive"))
      (node (ref "JP3") (pin "1") (pinfunction "1_1") (pintype "passive"))
      (node (ref "JP4") (pin "1") (pinfunction "1_1") (pintype "passive"))
      (node (ref "JP5") (pin "1") (pinfunction "1_1") (pintype "passive"))
      (node (ref "JP6") (pin "2") (pinfunction "2_2") (pintype "passive"))
      (node (ref "JP7") (pin "2") (pinfunction "2_2") (pintype "passive"))
      (node (ref "LCD1") (pin "2-VCC") (pinfunction "VCC_2-VCC") (pintype "bidirectional"))
      (node (ref "R53") (pin "1") (pinfunction "1_1") (pintype "passive"))
      (node (ref "U12") (pin "8") (pinfunction "VCC_8") (pintype "bidirectional"))
      (node (ref "U15") (pin "5") (pinfunction "VCC_5") (pintype "bidirectional"))
      (node (ref "U16") (pin "1") (pinfunction "VO_1") (pintype "bidirectional"))
      (node (ref "U17") (pin "3V3") (pinfunction "3V3_3V3") (pintype "bidirectional"))
      (node (ref "U17") (pin "3V3_2") (pinfunction "3V3_2_3V3_2") (pintype "bidirectional"))
      (node (ref "U18") (pin "5") (pinfunction "VCC_5") (pintype "bidirectional"))
    )
    (net (code "3") (name "5V") (class "Default")
      (node (ref "C14") (pin "1") (pinfunction "1_1") (pintype "passive"))
      (node (ref "C17") (pin "1") (pinfunction "1_1") (pintype "passive"))
      (node (ref "C18") (pin "1") (pinfunction "1_1") (pintype "passive"))
      (node (ref "C2") (pin "1") (pinfunction "1_1") (pintype "passive"))
      (node (ref "C32") (pin "1") (pinfunction "1_1") (pintype "passive"))
      (node (ref "C35") (pin "1") (pinfunction "1_1") (pintype "passive"))
      (node (ref "C4") (pin "1") (pinfunction "1_1") (pintype "passive"))
      (node (ref "C6") (pin "1") (pinfunction "1_1") (pintype "passive"))
      (node (ref "J2") (pin "1") (pinfunction "1_1") (pintype "passive"))
      (node (ref "JP6") (pin "1") (pinfunction "1_1") (pintype "passive"))
      (node (ref "JP7") (pin "3") (pinfunction "3_3") (pintype "passive"))
      (node (ref "LED7") (pin "1-VDD") (pinfunction "VDD_1-VDD") (pintype "bidirectional"))
      (node (ref "LED8") (pin "1-VDD") (pinfunction "VDD_1-VDD") (pintype "bidirectional"))
      (node (ref "R25") (pin "1") (pinfunction "1_1") (pintype "passive"))
      (node (ref "R41") (pin "1") (pinfunction "1_1") (pintype "passive"))
      (node (ref "R48") (pin "1") (pinfunction "1_1") (pintype "passive"))
      (node (ref "R71") (pin "1") (pinfunction "1_1") (pintype "passive"))
      (node (ref "R78") (pin "1") (pinfunction "1_1") (pintype "passive"))
      (node (ref "R79") (pin "1") (pinfunction "1_1") (pintype "passive"))
      (node (ref "U1") (pin "3") (pinfunction "VCC_3") (pintype "bidirectional"))
      (node (ref "U13") (pin "5") (pinfunction "VDD_5") (pintype "bidirectional"))
      (node (ref "U14") (pin "5") (pinfunction "VDD_5") (pintype "bidirectional"))
      (node (ref "U16") (pin "3") (pinfunction "VIN_3") (pintype "bidirectional"))
      (node (ref "U2") (pin "2") (pinfunction "VO_2") (pintype "bidirectional"))
      (node (ref "U2") (pin "4") (pinfunction "VO_4") (pintype "bidirectional"))
      (node (ref "U4") (pin "5") (pinfunction "VDD_5") (pintype "bidirectional"))
      (node (ref "U8") (pin "3") (pinfunction "VCC_3") (pintype "bidirectional"))
      (node (ref "U9") (pin "5") (pinfunction "VDD_5") (pintype "bidirectional"))
    )
    (net (code "4") (name "5V_USB") (class "Default")
      (node (ref "C29") (pin "1") (pinfunction "1_1") (pintype "passive"))
      (node (ref "R48") (pin "2") (pinfunction "2_2") (pintype "passive"))
      (node (ref "U17") (pin "5V") (pinfunction "5V_5V") (pintype "bidirectional"))
    )
    (net (code "5") (name "7V4") (class "Default")
      (node (ref "C1") (pin "1") (pinfunction "1_1") (pintype "passive"))
      (node (ref "C10") (pin "+") (pinfunction "+_+") (pintype "passive"))
      (node (ref "C12") (pin "1") (pinfunction "1_1") (pintype "passive"))
      (node (ref "C19") (pin "1") (pinfunction "1_1") (pintype "passive"))
      (node (ref "C24") (pin "1") (pinfunction "1_1") (pintype "passive"))
      (node (ref "C3") (pin "1") (pinfunction "1_1") (pintype "passive"))
      (node (ref "C7") (pin "+") (pinfunction "+_+") (pintype "passive"))
      (node (ref "D1") (pin "A") (pinfunction "ANODE_A") (pintype "passive"))
      (node (ref "D20") (pin "A") (pinfunction "ANODE_A") (pintype "passive"))
      (node (ref "D9") (pin "K") (pinfunction "CATHODE_K") (pintype "passive"))
      (node (ref "LED3") (pin "A") (pinfunction "A_A") (pintype "passive"))
      (node (ref "LED6") (pin "A") (pinfunction "A_A") (pintype "passive"))
      (node (ref "Q2") (pin "5") (pinfunction "D_5") (pintype "bidirectional"))
      (node (ref "Q2") (pin "6") (pinfunction "D_6") (pintype "bidirectional"))
      (node (ref "Q2") (pin "7") (pinfunction "D_7") (pintype "bidirectional"))
      (node (ref "Q2") (pin "8") (pinfunction "D_8") (pintype "bidirectional"))
      (node (ref "Q3") (pin "5") (pinfunction "D_5") (pintype "bidirectional"))
      (node (ref "Q3") (pin "6") (pinfunction "D_6") (pintype "bidirectional"))
      (node (ref "Q3") (pin "7") (pinfunction "D_7") (pintype "bidirectional"))
      (node (ref "Q3") (pin "8") (pinfunction "D_8") (pintype "bidirectional"))
      (node (ref "R22") (pin "2") (pinfunction "2_2") (pintype "passive"))
      (node (ref "R5") (pin "1") (pinfunction "1_1") (pintype "passive"))
      (node (ref "R58") (pin "2") (pinfunction "2_2") (pintype "passive"))
      (node (ref "R71") (pin "2") (pinfunction "2_2") (pintype "passive"))
      (node (ref "R9") (pin "1") (pinfunction "1_1") (pintype "passive"))
      (node (ref "TP9") (pin "1") (pinfunction "1_1") (pintype "bidirectional"))
      (node (ref "U2") (pin "3") (pinfunction "VIN_3") (pintype "bidirectional"))
      (node (ref "U21") (pin "4") (pinfunction "VCC_4") (pintype "bidirectional"))
      (node (ref "U3") (pin "4") (pinfunction "VCC_4") (pintype "bidirectional"))
    )
    (net (code "6") (name "7V4_SNS") (class "Default")
      (node (ref "C27") (pin "1") (pinfunction "1_1") (pintype "passive"))
      (node (ref "R13") (pin "2") (pinfunction "2_2") (pintype "passive"))
      (node (ref "R9") (pin "2") (pinfunction "2_2") (pintype "passive"))
      (node (ref "U18") (pin "3") (pinfunction "1_3") (pintype "bidirectional"))
    )
    (net (code "7") (name "AUX_SNS") (class "Default")
      (node (ref "R15") (pin "2") (pinfunction "2_2") (pintype "passive"))
      (node (ref "U15") (pin "4") (pinfunction "COM_4") (pintype "bidirectional"))
      (node (ref "U17") (pin "A4") (pinfunction "A4_A4") (pintype "bidirectional"))
    )
    (net (code "8") (name "AUX_SNS_INT") (class "Default")
      (node (ref "R15") (pin "1") (pinfunction "1_1") (pintype "passive"))
      (node (ref "U15") (pin "1") (pinfunction "2_1") (pintype "bidirectional"))
      (node (ref "U18") (pin "4") (pinfunction "COM_4") (pintype "bidirectional"))
    )
    (net (code "9") (name "C1+") (class "Default")
      (node (ref "BAT1") (pin "1+") (pinfunction "C1+_1+") (pintype "bidirectional"))
      (node (ref "R30") (pin "2") (pinfunction "2_2") (pintype "passive"))
      (node (ref "R82") (pin "2") (pinfunction "2_2") (pintype "passive"))
      (node (ref "U1") (pin "4") (pinfunction "IN+_4") (pintype "bidirectional"))
    )
    (net (code "10") (name "C1-") (class "Default")
      (node (ref "BAT1") (pin "1-") (pinfunction "C1-_1-") (pintype "bidirectional"))
      (node (ref "F1") (pin "2") (pinfunction "2_2") (pintype "bidirectional"))
      (node (ref "F3") (pin "1") (pinfunction "1_1") (pintype "passive"))
      (node (ref "R37") (pin "2") (pinfunction "2_2") (pintype "passive"))
      (node (ref "R54") (pin "2") (pinfunction "2_2") (pintype "passive"))
    )
    (net (code "11") (name "C1A") (class "Default")
      (node (ref "C50") (pin "1") (pinfunction "1_1") (pintype "passive"))
      (node (ref "R12") (pin "2") (pinfunction "2_2") (pintype "passive"))
      (node (ref "TP6") (pin "1") (pinfunction "1_1") (pintype "bidirectional"))
      (node (ref "U17") (pin "B1") (pinfunction "B1_B1") (pintype "bidirectional"))
    )
    (net (code "12") (name "C1CCPWM") (class "Default")
      (node (ref "R62") (pin "1") (pinfunction "1_1") (pintype "passive"))
      (node (ref "R74") (pin "1") (pinfunction "1_1") (pintype "passive"))
      (node (ref "U17") (pin "B6") (pinfunction "B6_B6") (pintype "bidirectional"))
    )
    (net (code "13") (name "C1CCSET") (class "Default")
      (node (ref "C31") (pin "1") (pinfunction "1_1") (pintype "passive"))
      (node (ref "R35") (pin "1") (pinfunction "1_1") (pintype "passive"))
      (node (ref "R61") (pin "2") (pinfunction "2_2") (pintype "passive"))
      (node (ref "TP10") (pin "1") (pinfunction "1_1") (pintype "bidirectional"))
      (node (ref "U13") (pin "3") (pinfunction "VIN+_3") (pintype "bidirectional"))
    )
    (net (code "14") (name "C1COFF") (class "Default")
      (node (ref "R45") (pin "1") (pinfunction "1_1") (pintype "passive"))
      (node (ref "U21") (pin "3") (pinfunction "/OD_3") (pintype "bidirectional"))
    )
    (net (code "15") (name "C1DFB") (class "Default")
      (node (ref "Q7") (pin "3") (pinfunction "S_3") (pintype "bidirectional"))
      (node (ref "R2") (pin "1") (pinfunction "1_1") (pintype "passive"))
      (node (ref "R63") (pin "1") (pinfunction "1_1") (pintype "passive"))
    )
    (net (code "16") (name "C1DOFF") (class "Default")
      (node (ref "D11") (pin "A") (pinfunction "ANODE_A") (pintype "passive"))
      (node (ref "R78") (pin "2") (pinfunction "2_2") (pintype "passive"))
      (node (ref "U17") (pin "B15") (pinfunction "B15_B15") (pintype "bidirectional"))
    )
    (net (code "17") (name "C1FET") (class "Default")
      (node (ref "R42") (pin "1") (pinfunction "1_1") (pintype "passive"))
      (node (ref "U21") (pin "2") (pinfunction "IN_2") (pintype "bidirectional"))
    )
    (net (code "18") (name "C1N") (class "Default")
      (node (ref "C44") (pin "2") (pinfunction "2_2") (pintype "passive"))
      (node (ref "L1") (pin "1") (pinfunction "P$1_1") (pintype "passive"))
      (node (ref "L3") (pin "P$1") (pinfunction "P$1_P$1") (pintype "passive"))
      (node (ref "Q10") (pin "5") (pinfunction "D_5") (pintype "bidirectional"))
      (node (ref "Q10") (pin "6") (pinfunction "D_6") (pintype "bidirectional"))
      (node (ref "Q10") (pin "7") (pinfunction "D_7") (pintype "bidirectional"))
      (node (ref "Q10") (pin "8") (pinfunction "D_8") (pintype "bidirectional"))
      (node (ref "Q2") (pin "1") (pinfunction "S_1") (pintype "bidirectional"))
      (node (ref "Q2") (pin "2") (pinfunction "S_2") (pintype "bidirectional"))
      (node (ref "Q2") (pin "3") (pinfunction "S_3") (pintype "bidirectional"))
      (node (ref "U21") (pin "7") (pinfunction "SWN_7") (pintype "bidirectional"))
    )
    (net (code "19") (name "C1NGATE") (class "Default")
      (node (ref "C15") (pin "2") (pinfunction "2_2") (pintype "passive"))
      (node (ref "R35") (pin "2") (pinfunction "2_2") (pintype "passive"))
      (node (ref "R43") (pin "2") (pinfunction "2_2") (pintype "passive"))
      (node (ref "R50") (pin "1") (pinfunction "1_1") (pintype "passive"))
      (node (ref "U13") (pin "1") (pinfunction "VOUT_1") (pintype "bidirectional"))
    )
    (net (code "20") (name "C1ON") (class "Default")
      (node (ref "D7") (pin "A") (pinfunction "ANODE_A") (pintype "passive"))
      (node (ref "R72") (pin "1") (pinfunction "1_1") (pintype "passive"))
      (node (ref "U17") (pin "B14") (pinfunction "B14_B14") (pintype "bidirectional"))
    )
    (net (code "21") (name "C1R") (class "Default")
      (node (ref "R37") (pin "1") (pinfunction "1_1") (pintype "passive"))
      (node (ref "R39") (pin "2") (pinfunction "2_2") (pintype "passive"))
      (node (ref "U17") (pin "A1") (pinfunction "A1_A1") (pintype "bidirectional"))
    )
    (net (code "22") (name "C1TH") (class "Default")
      (node (ref "C39") (pin "1") (pinfunction "1_1") (pintype "passive"))
      (node (ref "R7") (pin "1") (pinfunction "1_1") (pintype "passive"))
      (node (ref "R8") (pin "1") (pinfunction "1_1") (pintype "passive"))
      (node (ref "U17") (pin "A3") (pinfunction "A3_A3") (pintype "bidirectional"))
    )
    (net (code "23") (name "C1V") (class "Default")
      (node (ref "C51") (pin "1") (pinfunction "1_1") (pintype "passive"))
      (node (ref "R16") (pin "2") (pinfunction "2_2") (pintype "passive"))
      (node (ref "U17") (pin "B0") (pinfunction "B0_B0") (pintype "bidirectional"))
    )
    (net (code "24") (name "C2+") (class "Default")
      (node (ref "BAT3") (pin "1+") (pinfunction "C1+_1+") (pintype "bidirectional"))
      (node (ref "R57") (pin "2") (pinfunction "2_2") (pintype "passive"))
      (node (ref "R86") (pin "2") (pinfunction "2_2") (pintype "passive"))
      (node (ref "U8") (pin "4") (pinfunction "IN+_4") (pintype "bidirectional"))
    )
    (net (code "25") (name "C2-") (class "Default")
      (node (ref "BAT3") (pin "1-") (pinfunction "C1-_1-") (pintype "bidirectional"))
      (node (ref "F2") (pin "2") (pinfunction "2_2") (pintype "bidirectional"))
      (node (ref "F4") (pin "1") (pinfunction "1_1") (pintype "passive"))
      (node (ref "R38") (pin "2") (pinfunction "2_2") (pintype "passive"))
      (node (ref "R84") (pin "2") (pinfunction "2_2") (pintype "passive"))
    )
    (net (code "26") (name "C2A") (class "Default")
      (node (ref "C48") (pin "1") (pinfunction "1_1") (pintype "passive"))
      (node (ref "R24") (pin "2") (pinfunction "2_2") (pintype "passive"))
      (node (ref "TP8") (pin "1") (pinfunction "1_1") (pintype "bidirectional"))
      (node (ref "U17") (pin "A7") (pinfunction "A7_A7") (pintype "bidirectional"))
    )
    (net (code "27") (name "C2CCPWM") (class "Default")
      (node (ref "R69") (pin "1") (pinfunction "1_1") (pintype "passive"))
      (node (ref "R75") (pin "1") (pinfunction "1_1") (pintype "passive"))
      (node (ref "U17") (pin "B7") (pinfunction "B7_B7") (pintype "bidirectional"))
    )
    (net (code "28") (name "C2CCSET") (class "Default")
      (node (ref "C34") (pin "1") (pinfunction "1_1") (pintype "passive"))
      (node (ref "R59") (pin "1") (pinfunction "1_1") (pintype "passive"))
      (node (ref "R66") (pin "2") (pinfunction "2_2") (pintype "passive"))
      (node (ref "TP11") (pin "1") (pinfunction "1_1") (pintype "bidirectional"))
      (node (ref "U14") (pin "3") (pinfunction "VIN+_3") (pintype "bidirectional"))
    )
    (net (code "29") (name "C2COFF") (class "Default")
      (node (ref "R47") (pin "1") (pinfunction "1_1") (pintype "passive"))
      (node (ref "U3") (pin "3") (pinfunction "/OD_3") (pintype "bidirectional"))
    )
    (net (code "30") (name "C2DFB") (class "Default")
      (node (ref "Q8") (pin "3") (pinfunction "S_3") (pintype "bidirectional"))
      (node (ref "R3") (pin "1") (pinfunction "1_1") (pintype "passive"))
      (node (ref "R67") (pin "1") (pinfunction "1_1") (pintype "passive"))
    )
    (net (code "31") (name "C2DOFF") (class "Default")
      (node (ref "D12") (pin "A") (pinfunction "ANODE_A") (pintype "passive"))
      (node (ref "R79") (pin "2") (pinfunction "2_2") (pintype "passive"))
      (node (ref "U17") (pin "A15") (pinfunction "A15_A15") (pintype "bidirectional"))
    )
    (net (code "32") (name "C2FET") (class "Default")
      (node (ref "R46") (pin "1") (pinfunction "1_1") (pintype "passive"))
      (node (ref "U3") (pin "2") (pinfunction "IN_2") (pintype "bidirectional"))
    )
    (net (code "33") (name "C2N") (class "Default")
      (node (ref "C13") (pin "2") (pinfunction "2_2") (pintype "passive"))
      (node (ref "L2") (pin "1") (pinfunction "P$1_1") (pintype "passive"))
      (node (ref "L4") (pin "P$1") (pinfunction "P$1_P$1") (pintype "passive"))
      (node (ref "Q13") (pin "5") (pinfunction "D_5") (pintype "bidirectional"))
      (node (ref "Q13") (pin "6") (pinfunction "D_6") (pintype "bidirectional"))
      (node (ref "Q13") (pin "7") (pinfunction "D_7") (pintype "bidirectional"))
      (node (ref "Q13") (pin "8") (pinfunction "D_8") (pintype "bidirectional"))
      (node (ref "Q3") (pin "1") (pinfunction "S_1") (pintype "bidirectional"))
      (node (ref "Q3") (pin "2") (pinfunction "S_2") (pintype "bidirectional"))
      (node (ref "Q3") (pin "3") (pinfunction "S_3") (pintype "bidirectional"))
      (node (ref "U3") (pin "7") (pinfunction "SWN_7") (pintype "bidirectional"))
    )
    (net (code "34") (name "C2NGATE") (class "Default")
      (node (ref "C33") (pin "2") (pinfunction "2_2") (pintype "passive"))
      (node (ref "R44") (pin "2") (pinfunction "2_2") (pintype "passive"))
      (node (ref "R51") (pin "1") (pinfunction "1_1") (pintype "passive"))
      (node (ref "R59") (pin "2") (pinfunction "2_2") (pintype "passive"))
      (node (ref "U14") (pin "1") (pinfunction "VOUT_1") (pintype "bidirectional"))
    )
    (net (code "35") (name "C2ON") (class "Default")
      (node (ref "D8") (pin "A") (pinfunction "ANODE_A") (pintype "passive"))
      (node (ref "R73") (pin "1") (pinfunction "1_1") (pintype "passive"))
      (node (ref "U17") (pin "B3") (pinfunction "B3_B3") (pintype "bidirectional"))
    )
    (net (code "36") (name "C2R") (class "Default")
      (node (ref "R38") (pin "1") (pinfunction "1_1") (pintype "passive"))
      (node (ref "R40") (pin "2") (pinfunction "2_2") (pintype "passive"))
      (node (ref "U17") (pin "A0") (pinfunction "A0_A0") (pintype "bidirectional"))
    )
    (net (code "37") (name "C2TH") (class "Default")
      (node (ref "C40") (pin "1") (pinfunction "1_1") (pintype "passive"))
      (node (ref "R31") (pin "1") (pinfunction "1_1") (pintype "passive"))
      (node (ref "R32") (pin "1") (pinfunction "1_1") (pintype "passive"))
      (node (ref "U17") (pin "A2") (pinfunction "A2_A2") (pintype "bidirectional"))
    )
    (net (code "38") (name "C2V") (class "Default")
      (node (ref "C49") (pin "1") (pinfunction "1_1") (pintype "passive"))
      (node (ref "R33") (pin "2") (pinfunction "2_2") (pintype "passive"))
      (node (ref "U17") (pin "A6") (pinfunction "A6_A6") (pintype "bidirectional"))
    )
    (net (code "39") (name "DI") (class "Default")
      (node (ref "Q16") (pin "1") (pinfunction "G_1") (pintype "bidirectional"))
      (node (ref "U17") (pin "B13") (pinfunction "B13_B13") (pintype "bidirectional"))
    )
    (net (code "40") (name "DI2") (class "Default")
      (node (ref "LED7") (pin "2-DOUT") (pinfunction "DOUT_2-DOUT") (pintype "output"))
      (node (ref "LED8") (pin "4-DIN") (pinfunction "DIN_4-DIN") (pintype "input"))
    )
    (net (code "41") (name "FANON") (class "Default")
      (node (ref "Q9") (pin "1") (pinfunction "G_1") (pintype "bidirectional"))
      (node (ref "R34") (pin "2") (pinfunction "2_2") (pintype "passive"))
      (node (ref "U17") (pin "B4") (pinfunction "B4_B4") (pintype "bidirectional"))
    )
    (net (code "42") (name "GND") (class "Default")
      (node (ref "C1") (pin "2") (pinfunction "2_2") (pintype "passive"))
      (node (ref "C10") (pin "-") (pinfunction "-_-") (pintype "passive"))
      (node (ref "C11") (pin "2") (pinfunction "2_2") (pintype "passive"))
      (node (ref "C12") (pin "2") (pinfunction "2_2") (pintype "passive"))
      (node (ref "C14") (pin "2") (pinfunction "2_2") (pintype "passive"))
      (node (ref "C16") (pin "2") (pinfunction "2_2") (pintype "passive"))
      (node (ref "C17") (pin "2") (pinfunction "2_2") (pintype "passive"))
      (node (ref "C18") (pin "2") (pinfunction "2_2") (pintype "passive"))
      (node (ref "C19") (pin "2") (pinfunction "2_2") (pintype "passive"))
      (node (ref "C2") (pin "2") (pinfunction "2_2") (pintype "passive"))
      (node (ref "C20") (pin "2") (pinfunction "2_2") (pintype "passive"))
      (node (ref "C21") (pin "-") (pinfunction "-_-") (pintype "passive"))
      (node (ref "C22") (pin "-") (pinfunction "-_-") (pintype "passive"))
      (node (ref "C23") (pin "2") (pinfunction "2_2") (pintype "passive"))
      (node (ref "C24") (pin "2") (pinfunction "2_2") (pintype "passive"))
      (node (ref "C26") (pin "-") (pinfunction "-_-") (pintype "passive"))
      (node (ref "C27") (pin "2") (pinfunction "2_2") (pintype "passive"))
      (node (ref "C28") (pin "2") (pinfunction "2_2") (pintype "passive"))
      (node (ref "C29") (pin "2") (pinfunction "2_2") (pintype "passive"))
      (node (ref "C3") (pin "2") (pinfunction "2_2") (pintype "passive"))
      (node (ref "C30") (pin "2") (pinfunction "2_2") (pintype "passive"))
      (node (ref "C31") (pin "2") (pinfunction "2_2") (pintype "passive"))
      (node (ref "C32") (pin "2") (pinfunction "2_2") (pintype "passive"))
      (node (ref "C34") (pin "2") (pinfunction "2_2") (pintype "passive"))
      (node (ref "C35") (pin "2") (pinfunction "2_2") (pintype "passive"))
      (node (ref "C36") (pin "2") (pinfunction "2_2") (pintype "passive"))
      (node (ref "C37") (pin "2") (pinfunction "2_2") (pintype "passive"))
      (node (ref "C38") (pin "2") (pinfunction "2_2") (pintype "passive"))
      (node (ref "C39") (pin "2") (pinfunction "2_2") (pintype "passive"))
      (node (ref "C4") (pin "2") (pinfunction "2_2") (pintype "passive"))
      (node (ref "C40") (pin "2") (pinfunction "2_2") (pintype "passive"))
      (node (ref "C41") (pin "2") (pinfunction "2_2") (pintype "passive"))
      (node (ref "C42") (pin "2") (pinfunction "2_2") (pintype "passive"))
      (node (ref "C43") (pin "2") (pinfunction "2_2") (pintype "passive"))
      (node (ref "C48") (pin "2") (pinfunction "2_2") (pintype "passive"))
      (node (ref "C49") (pin "2") (pinfunction "2_2") (pintype "passive"))
      (node (ref "C5") (pin "2") (pinfunction "2_2") (pintype "passive"))
      (node (ref "C50") (pin "2") (pinfunction "2_2") (pintype "passive"))
      (node (ref "C51") (pin "2") (pinfunction "2_2") (pintype "passive"))
      (node (ref "C6") (pin "2") (pinfunction "2_2") (pintype "passive"))
      (node (ref "C7") (pin "-") (pinfunction "-_-") (pintype "passive"))
      (node (ref "C8") (pin "-") (pinfunction "-_-") (pintype "passive"))
      (node (ref "C9") (pin "2") (pinfunction "2_2") (pintype "passive"))
      (node (ref "D9") (pin "A") (pinfunction "ANODE_A") (pintype "passive"))
      (node (ref "J1") (pin "1") (pinfunction "1_1") (pintype "passive"))
      (node (ref "JP1") (pin "1") (pinfunction "1_1") (pintype "passive"))
      (node (ref "JP2") (pin "3") (pinfunction "3_3") (pintype "passive"))
      (node (ref "JP3") (pin "3") (pinfunction "3_3") (pintype "passive"))
      (node (ref "JP4") (pin "3") (pinfunction "3_3") (pintype "passive"))
      (node (ref "JP5") (pin "3") (pinfunction "3_3") (pintype "passive"))
      (node (ref "LCD1") (pin "1=GND") (pinfunction "GND_1=GND") (pintype "bidirectional"))
      (node (ref "LED7") (pin "3-GND") (pinfunction "GND_3-GND") (pintype "bidirectional"))
      (node (ref "LED8") (pin "3-GND") (pinfunction "GND_3-GND") (pintype "bidirectional"))
      (node (ref "Q10") (pin "1") (pinfunction "S_1") (pintype "bidirectional"))
      (node (ref "Q10") (pin "2") (pinfunction "S_2") (pintype "bidirectional"))
      (node (ref "Q10") (pin "3") (pinfunction "S_3") (pintype "bidirectional"))
      (node (ref "Q11") (pin "1") (pinfunction "S_1") (pintype "bidirectional"))
      (node (ref "Q11") (pin "2") (pinfunction "S_2") (pintype "bidirectional"))
      (node (ref "Q11") (pin "3") (pinfunction "S_3") (pintype "bidirectional"))
      (node (ref "Q12") (pin "1") (pinfunction "S_1") (pintype "bidirectional"))
      (node (ref "Q12") (pin "2") (pinfunction "S_2") (pintype "bidirectional"))
      (node (ref "Q12") (pin "3") (pinfunction "S_3") (pintype "bidirectional"))
      (node (ref "Q13") (pin "1") (pinfunction "S_1") (pintype "bidirectional"))
      (node (ref "Q13") (pin "2") (pinfunction "S_2") (pintype "bidirectional"))
      (node (ref "Q13") (pin "3") (pinfunction "S_3") (pintype "bidirectional"))
      (node (ref "Q16") (pin "2") (pinfunction "S_2") (pintype "bidirectional"))
      (node (ref "Q9") (pin "2") (pinfunction "S_2") (pintype "bidirectional"))
      (node (ref "R11") (pin "2") (pinfunction "2_2") (pintype "passive"))
      (node (ref "R13") (pin "1") (pinfunction "1_1") (pintype "passive"))
      (node (ref "R19") (pin "1") (pinfunction "1_1") (pintype "passive"))
      (node (ref "R2") (pin "2") (pinfunction "2_2") (pintype "passive"))
      (node (ref "R23") (pin "1") (pinfunction "1_1") (pintype "passive"))
      (node (ref "R27") (pin "1") (pinfunction "1_1") (pintype "passive"))
      (node (ref "R3") (pin "2") (pinfunction "2_2") (pintype "passive"))
      (node (ref "R32") (pin "2") (pinfunction "2_2") (pintype "passive"))
      (node (ref "R34") (pin "1") (pinfunction "1_1") (pintype "passive"))
      (node (ref "R36") (pin "1") (pinfunction "1_1") (pintype "passive"))
      (node (ref "R39") (pin "1") (pinfunction "1_1") (pintype "passive"))
      (node (ref "R4") (pin "2") (pinfunction "2_2") (pintype "passive"))
      (node (ref "R40") (pin "1") (pinfunction "1_1") (pintype "passive"))
      (node (ref "R49") (pin "2") (pinfunction "2_2") (pintype "passive"))
      (node (ref "R50") (pin "2") (pinfunction "2_2") (pintype "passive"))
      (node (ref "R51") (pin "2") (pinfunction "2_2") (pintype "passive"))
      (node (ref "R52") (pin "1") (pinfunction "1_1") (pintype "passive"))
      (node (ref "R56") (pin "2") (pinfunction "2_2") (pintype "passive"))
      (node (ref "R6") (pin "2") (pinfunction "2_2") (pintype "passive"))
      (node (ref "R60") (pin "2") (pinfunction "2_2") (pintype "passive"))
      (node (ref "R65") (pin "1") (pinfunction "1_1") (pintype "passive"))
      (node (ref "R70") (pin "1") (pinfunction "1_1") (pintype "passive"))
      (node (ref "R72") (pin "2") (pinfunction "2_2") (pintype "passive"))
      (node (ref "R73") (pin "2") (pinfunction "2_2") (pintype "passive"))
      (node (ref "R74") (pin "2") (pinfunction "2_2") (pintype "passive"))
      (node (ref "R75") (pin "2") (pinfunction "2_2") (pintype "passive"))
      (node (ref "R76") (pin "2") (pinfunction "2_2") (pintype "passive"))
      (node (ref "R8") (pin "2") (pinfunction "2_2") (pintype "passive"))
      (node (ref "R80") (pin "2") (pinfunction "2_2") (pintype "passive"))
      (node (ref "R81") (pin "2") (pinfunction "2_2") (pintype "passive"))
      (node (ref "R89") (pin "1") (pinfunction "1_1") (pintype "passive"))
      (node (ref "S1") (pin "3") (pinfunction "3_3") (pintype "passive"))
      (node (ref "S1") (pin "4") (pinfunction "4_4") (pintype "passive"))
      (node (ref "S2") (pin "3") (pinfunction "3_3") (pintype "passive"))
      (node (ref "S2") (pin "4") (pinfunction "4_4") (pintype "passive"))
      (node (ref "T1") (pin "1") (pinfunction "1_1") (pintype "bidirectional"))
      (node (ref "T2") (pin "1") (pinfunction "1_1") (pintype "bidirectional"))
      (node (ref "U1") (pin "2") (pinfunction "GND_2") (pintype "bidirectional"))
      (node (ref "U12") (pin "4") (pinfunction "GND_4") (pintype "bidirectional"))
      (node (ref "U13") (pin "2") (pinfunction "VSS_2") (pintype "bidirectional"))
      (node (ref "U14") (pin "2") (pinfunction "VSS_2") (pintype "bidirectional"))
      (node (ref "U15") (pin "2") (pinfunction "GND_2") (pintype "bidirectional"))
      (node (ref "U16") (pin "2") (pinfunction "GND_2") (pintype "bidirectional"))
      (node (ref "U16") (pin "2@1") (pinfunction "GND_2@1") (pintype "bidirectional"))
      (node (ref "U17") (pin "GND") (pinfunction "GND_GND") (pintype "bidirectional"))
      (node (ref "U17") (pin "GND2") (pinfunction "GND2_GND2") (pintype "bidirectional"))
      (node (ref "U17") (pin "GND4") (pinfunction "GND4_GND4") (pintype "bidirectional"))
      (node (ref "U18") (pin "2") (pinfunction "GND_2") (pintype "bidirectional"))
      (node (ref "U2") (pin "1") (pinfunction "GND_1") (pintype "bidirectional"))
      (node (ref "U21") (pin "6") (pinfunction "PGND_6") (pintype "bidirectional"))
      (node (ref "U3") (pin "6") (pinfunction "PGND_6") (pintype "bidirectional"))
      (node (ref "U4") (pin "2") (pinfunction "VSS_2") (pintype "bidirectional"))
      (node (ref "U6") (pin "3") (pinfunction "A_3") (pintype "passive"))
      (node (ref "U8") (pin "2") (pinfunction "GND_2") (pintype "bidirectional"))
      (node (ref "U9") (pin "2") (pinfunction "VSS_2") (pintype "bidirectional"))
    )
    (net (code "43") (name "HSTH") (class "Default")
      (node (ref "C41") (pin "1") (pinfunction "1_1") (pintype "passive"))
      (node (ref "R77") (pin "1") (pinfunction "1_1") (pintype "passive"))
      (node (ref "T1") (pin "2") (pinfunction "2_2") (pintype "bidirectional"))
      (node (ref "U18") (pin "1") (pinfunction "2_1") (pintype "bidirectional"))
    )
    (net (code "44") (name "HSTH2") (class "Default")
      (node (ref "C43") (pin "1") (pinfunction "1_1") (pintype "passive"))
      (node (ref "R14") (pin "1") (pinfunction "1_1") (pintype "passive"))
      (node (ref "T2") (pin "2") (pinfunction "2_2") (pintype "bidirectional"))
      (node (ref "U15") (pin "3") (pinfunction "1_3") (pintype "bidirectional"))
    )
    (net (code "45") (name "ISNS_REF") (class "Default")
      (node (ref "C11") (pin "1") (pinfunction "1_1") (pintype "passive"))
      (node (ref "C16") (pin "1") (pinfunction "1_1") (pintype "passive"))
      (node (ref "C28") (pin "1") (pinfunction "1_1") (pintype "passive"))
      (node (ref "R10") (pin "2") (pinfunction "2_2") (pintype "passive"))
      (node (ref "R11") (pin "1") (pinfunction "1_1") (pintype "passive"))
      (node (ref "TP5") (pin "1") (pinfunction "1_1") (pintype "bidirectional"))
      (node (ref "TP7") (pin "1") (pinfunction "1_1") (pintype "bidirectional"))
      (node (ref "U1") (pin "1") (pinfunction "REF_1") (pintype "bidirectional"))
      (node (ref "U17") (pin "A5") (pinfunction "A5_A5") (pintype "bidirectional"))
      (node (ref "U8") (pin "1") (pinfunction "REF_1") (pintype "bidirectional"))
    )
    (net (code "46") (name "NGATE1") (class "Default")
      (node (ref "LED4") (pin "A") (pinfunction "A_A") (pintype "passive"))
      (node (ref "Q10") (pin "4") (pinfunction "G_4") (pintype "bidirectional"))
      (node (ref "R56") (pin "1") (pinfunction "1_1") (pintype "passive"))
      (node (ref "U21") (pin "5") (pinfunction "DRVL_5") (pintype "bidirectional"))
    )
    (net (code "47") (name "NGATE2") (class "Default")
      (node (ref "LED5") (pin "A") (pinfunction "A_A") (pintype "passive"))
      (node (ref "Q13") (pin "4") (pinfunction "G_4") (pintype "bidirectional"))
      (node (ref "R60") (pin "1") (pinfunction "1_1") (pintype "passive"))
      (node (ref "U3") (pin "5") (pinfunction "DRVL_5") (pintype "bidirectional"))
    )
    (net (code "48") (name "Net-(C15-Pad1)") (class "Default")
      (node (ref "C15") (pin "1") (pinfunction "1_1") (pintype "passive"))
      (node (ref "R64") (pin "2") (pinfunction "2_2") (pintype "passive"))
    )
    (net (code "49") (name "Net-(C33-Pad1)") (class "Default")
      (node (ref "C33") (pin "1") (pinfunction "1_1") (pintype "passive"))
      (node (ref "R68") (pin "2") (pinfunction "2_2") (pintype "passive"))
    )
    (net (code "50") (name "Net-(D1-CATHODE)") (class "Default")
      (node (ref "C13") (pin "1") (pinfunction "1_1") (pintype "passive"))
      (node (ref "D1") (pin "K") (pinfunction "CATHODE_K") (pintype "passive"))
      (node (ref "U3") (pin "1") (pinfunction "BST_1") (pintype "bidirectional"))
    )
    (net (code "51") (name "Net-(D5-CATHODE)") (class "Default")
      (node (ref "D5") (pin "K") (pinfunction "CATHODE_K") (pintype "passive"))
      (node (ref "D7") (pin "K") (pinfunction "CATHODE_K") (pintype "passive"))
      (node (ref "Q11") (pin "4") (pinfunction "G_4") (pintype "bidirectional"))
      (node (ref "R23") (pin "2") (pinfunction "2_2") (pintype "passive"))
    )
    (net (code "52") (name "Net-(D6-CATHODE)") (class "Default")
      (node (ref "D6") (pin "K") (pinfunction "CATHODE_K") (pintype "passive"))
      (node (ref "D8") (pin "K") (pinfunction "CATHODE_K") (pintype "passive"))
      (node (ref "Q12") (pin "4") (pinfunction "G_4") (pintype "bidirectional"))
      (node (ref "R36") (pin "2") (pinfunction "2_2") (pintype "passive"))
    )
    (net (code "53") (name "Net-(D11-CATHODE)") (class "Default")
      (node (ref "D11") (pin "K") (pinfunction "CATHODE_K") (pintype "passive"))
      (node (ref "R63") (pin "2") (pinfunction "2_2") (pintype "passive"))
      (node (ref "R64") (pin "1") (pinfunction "1_1") (pintype "passive"))
      (node (ref "U13") (pin "4") (pinfunction "VIN-_4") (pintype "bidirectional"))
    )
    (net (code "54") (name "Net-(D12-CATHODE)") (class "Default")
      (node (ref "D12") (pin "K") (pinfunction "CATHODE_K") (pintype "passive"))
      (node (ref "R67") (pin "2") (pinfunction "2_2") (pintype "passive"))
      (node (ref "R68") (pin "1") (pinfunction "1_1") (pintype "passive"))
      (node (ref "U14") (pin "4") (pinfunction "VIN-_4") (pintype "bidirectional"))
    )
    (net (code "55") (name "Net-(D20-CATHODE)") (class "Default")
      (node (ref "C44") (pin "1") (pinfunction "1_1") (pintype "passive"))
      (node (ref "D20") (pin "K") (pinfunction "CATHODE_K") (pintype "passive"))
      (node (ref "U21") (pin "1") (pinfunction "BST_1") (pintype "bidirectional"))
    )
    (net (code "56") (name "Net-(F1-Pad1)") (class "Default")
      (node (ref "F1") (pin "1") (pinfunction "1_1") (pintype "bidirectional"))
      (node (ref "F3") (pin "2") (pinfunction "2_2") (pintype "passive"))
      (node (ref "Q11") (pin "5") (pinfunction "D_5") (pintype "bidirectional"))
      (node (ref "Q11") (pin "6") (pinfunction "D_6") (pintype "bidirectional"))
      (node (ref "Q11") (pin "7") (pinfunction "D_7") (pintype "bidirectional"))
      (node (ref "Q11") (pin "8") (pinfunction "D_8") (pintype "bidirectional"))
    )
    (net (code "57") (name "Net-(F2-Pad1)") (class "Default")
      (node (ref "F2") (pin "1") (pinfunction "1_1") (pintype "bidirectional"))
      (node (ref "F4") (pin "2") (pinfunction "2_2") (pintype "passive"))
      (node (ref "Q12") (pin "5") (pinfunction "D_5") (pintype "bidirectional"))
      (node (ref "Q12") (pin "6") (pinfunction "D_6") (pintype "bidirectional"))
      (node (ref "Q12") (pin "7") (pinfunction "D_7") (pintype "bidirectional"))
      (node (ref "Q12") (pin "8") (pinfunction "D_8") (pintype "bidirectional"))
    )
    (net (code "58") (name "Net-(J1-Pad2)") (class "Default")
      (node (ref "J1") (pin "2") (pinfunction "2_2") (pintype "passive"))
      (node (ref "R22") (pin "1") (pinfunction "1_1") (pintype "passive"))
    )
    (net (code "59") (name "Net-(L1-P$2)") (class "Default")
      (node (ref "C26") (pin "+") (pinfunction "+_+") (pintype "passive"))
      (node (ref "C5") (pin "1") (pinfunction "1_1") (pintype "passive"))
      (node (ref "C8") (pin "+") (pinfunction "+_+") (pintype "passive"))
      (node (ref "L1") (pin "2") (pinfunction "P$2_2") (pintype "passive"))
      (node (ref "L3") (pin "P$2") (pinfunction "P$2_P$2") (pintype "passive"))
      (node (ref "R1") (pin "2") (pinfunction "2_2") (pintype "passive"))
    )
    (net (code "60") (name "Net-(L2-P$2)") (class "Default")
      (node (ref "C20") (pin "1") (pinfunction "1_1") (pintype "passive"))
      (node (ref "C21") (pin "+") (pinfunction "+_+") (pintype "passive"))
      (node (ref "C22") (pin "+") (pinfunction "+_+") (pintype "passive"))
      (node (ref "L2") (pin "2") (pinfunction "P$2_2") (pintype "passive"))
      (node (ref "L4") (pin "P$2") (pinfunction "P$2_P$2") (pintype "passive"))
      (node (ref "R17") (pin "2") (pinfunction "2_2") (pintype "passive"))
    )
    (net (code "61") (name "Net-(LED3-PadC)") (class "Default")
      (node (ref "LED3") (pin "C") (pinfunction "C_C") (pintype "passive"))
      (node (ref "R88") (pin "2") (pinfunction "2_2") (pintype "passive"))
    )
    (net (code "62") (name "Net-(LED4-PadC)") (class "Default")
      (node (ref "LED4") (pin "C") (pinfunction "C_C") (pintype "passive"))
      (node (ref "R52") (pin "2") (pinfunction "2_2") (pintype "passive"))
    )
    (net (code "63") (name "Net-(LED5-PadC)") (class "Default")
      (node (ref "LED5") (pin "C") (pinfunction "C_C") (pintype "passive"))
      (node (ref "R89") (pin "2") (pinfunction "2_2") (pintype "passive"))
    )
    (net (code "64") (name "Net-(LED6-PadC)") (class "Default")
      (node (ref "LED6") (pin "C") (pinfunction "C_C") (pintype "passive"))
      (node (ref "R90") (pin "2") (pinfunction "2_2") (pintype "passive"))
    )
    (net (code "65") (name "Net-(LED7-DIN)") (class "Default")
      (node (ref "LED7") (pin "4-DIN") (pinfunction "DIN_4-DIN") (pintype "input"))
      (node (ref "Q16") (pin "3") (pinfunction "D_3") (pintype "bidirectional"))
      (node (ref "R41") (pin "2") (pinfunction "2_2") (pintype "passive"))
    )
    (net (code "66") (name "Net-(LED8-DOUT)") (class "Default")
      (node (ref "JP8") (pin "1") (pinfunction "1_1") (pintype "passive"))
      (node (ref "LED8") (pin "2-DOUT") (pinfunction "DOUT_2-DOUT") (pintype "output"))
    )
    (net (code "67") (name "Net-(Q7-D)") (class "Default")
      (node (ref "Q7") (pin "2") (pinfunction "D_2") (pintype "bidirectional"))
      (node (ref "R1") (pin "1") (pinfunction "1_1") (pintype "passive"))
      (node (ref "R30") (pin "1") (pinfunction "1_1") (pintype "passive"))
      (node (ref "U1") (pin "5") (pinfunction "IN-_5") (pintype "bidirectional"))
    )
    (net (code "68") (name "Net-(Q7-G)") (class "Default")
      (node (ref "Q7") (pin "1") (pinfunction "G_1") (pintype "bidirectional"))
      (node (ref "R43") (pin "1") (pinfunction "1_1") (pintype "passive"))
    )
    (net (code "69") (name "Net-(Q8-D)") (class "Default")
      (node (ref "Q8") (pin "2") (pinfunction "D_2") (pintype "bidirectional"))
      (node (ref "R17") (pin "1") (pinfunction "1_1") (pintype "passive"))
      (node (ref "R57") (pin "1") (pinfunction "1_1") (pintype "passive"))
      (node (ref "U8") (pin "5") (pinfunction "IN-_5") (pintype "bidirectional"))
    )
    (net (code "70") (name "Net-(Q8-G)") (class "Default")
      (node (ref "Q8") (pin "1") (pinfunction "G_1") (pintype "bidirectional"))
      (node (ref "R44") (pin "1") (pinfunction "1_1") (pintype "passive"))
    )
    (net (code "71") (name "Net-(Q9-D)") (class "Default")
      (node (ref "J2") (pin "2") (pinfunction "2_2") (pintype "passive"))
      (node (ref "Q9") (pin "3") (pinfunction "D_3") (pintype "bidirectional"))
    )
    (net (code "72") (name "Net-(R61-Pad1)") (class "Default")
      (node (ref "R61") (pin "1") (pinfunction "1_1") (pintype "passive"))
      (node (ref "R62") (pin "2") (pinfunction "2_2") (pintype "passive"))
      (node (ref "R65") (pin "2") (pinfunction "2_2") (pintype "passive"))
    )
    (net (code "73") (name "Net-(R66-Pad1)") (class "Default")
      (node (ref "R66") (pin "1") (pinfunction "1_1") (pintype "passive"))
      (node (ref "R69") (pin "2") (pinfunction "2_2") (pintype "passive"))
      (node (ref "R70") (pin "2") (pinfunction "2_2") (pintype "passive"))
    )
    (net (code "74") (name "Net-(TP1-1)") (class "Default")
      (node (ref "R55") (pin "2") (pinfunction "2_2") (pintype "passive"))
      (node (ref "TP1") (pin "P$1") (pinfunction "1_P$1") (pintype "bidirectional"))
    )
    (net (code "75") (name "Net-(TP2-1)") (class "Default")
      (node (ref "R83") (pin "2") (pinfunction "2_2") (pintype "passive"))
      (node (ref "TP2") (pin "P$1") (pinfunction "1_P$1") (pintype "bidirectional"))
    )
    (net (code "76") (name "Net-(TP3-1)") (class "Default")
      (node (ref "R85") (pin "2") (pinfunction "2_2") (pintype "passive"))
      (node (ref "TP3") (pin "P$1") (pinfunction "1_P$1") (pintype "bidirectional"))
    )
    (net (code "77") (name "Net-(TP4-1)") (class "Default")
      (node (ref "R87") (pin "2") (pinfunction "2_2") (pintype "passive"))
      (node (ref "TP4") (pin "P$1") (pinfunction "1_P$1") (pintype "bidirectional"))
    )
    (net (code "78") (name "Net-(U1-OUT)") (class "Default")
      (node (ref "R12") (pin "1") (pinfunction "1_1") (pintype "passive"))
      (node (ref "U1") (pin "6") (pinfunction "OUT_6") (pintype "bidirectional"))
    )
    (net (code "79") (name "Net-(U4-VIN+)") (class "Default")
      (node (ref "R18") (pin "2") (pinfunction "2_2") (pintype "passive"))
      (node (ref "R19") (pin "2") (pinfunction "2_2") (pintype "passive"))
      (node (ref "U4") (pin "1") (pinfunction "VIN+_1") (pintype "bidirectional"))
    )
    (net (code "80") (name "Net-(U4-VIN-)") (class "Default")
      (node (ref "R20") (pin "2") (pinfunction "2_2") (pintype "passive"))
      (node (ref "R21") (pin "1") (pinfunction "1_1") (pintype "passive"))
      (node (ref "U4") (pin "3") (pinfunction "VIN-_3") (pintype "bidirectional"))
    )
    (net (code "81") (name "Net-(U4-VOUT)") (class "Default")
      (node (ref "R16") (pin "1") (pinfunction "1_1") (pintype "passive"))
      (node (ref "R21") (pin "2") (pinfunction "2_2") (pintype "passive"))
      (node (ref "U4") (pin "4") (pinfunction "VOUT_4") (pintype "bidirectional"))
    )
    (net (code "82") (name "Net-(U8-OUT)") (class "Default")
      (node (ref "R24") (pin "1") (pinfunction "1_1") (pintype "passive"))
      (node (ref "U8") (pin "6") (pinfunction "OUT_6") (pintype "bidirectional"))
    )
    (net (code "83") (name "Net-(U9-VIN+)") (class "Default")
      (node (ref "R26") (pin "2") (pinfunction "2_2") (pintype "passive"))
      (node (ref "R27") (pin "2") (pinfunction "2_2") (pintype "passive"))
      (node (ref "U9") (pin "1") (pinfunction "VIN+_1") (pintype "bidirectional"))
    )
    (net (code "84") (name "Net-(U9-VIN-)") (class "Default")
      (node (ref "R28") (pin "2") (pinfunction "2_2") (pintype "passive"))
      (node (ref "R29") (pin "1") (pinfunction "1_1") (pintype "passive"))
      (node (ref "U9") (pin "3") (pinfunction "VIN-_3") (pintype "bidirectional"))
    )
    (net (code "85") (name "Net-(U9-VOUT)") (class "Default")
      (node (ref "R29") (pin "2") (pinfunction "2_2") (pintype "passive"))
      (node (ref "R33") (pin "1") (pinfunction "1_1") (pintype "passive"))
      (node (ref "U9") (pin "4") (pinfunction "VOUT_4") (pintype "bidirectional"))
    )
    (net (code "86") (name "Net-(U12-A0)") (class "Default")
      (node (ref "JP3") (pin "2") (pinfunction "2_2") (pintype "passive"))
      (node (ref "U12") (pin "7") (pinfunction "A0_7") (pintype "bidirectional"))
    )
    (net (code "87") (name "Net-(U12-A1)") (class "Default")
      (node (ref "JP4") (pin "2") (pinfunction "2_2") (pintype "passive"))
      (node (ref "U12") (pin "6") (pinfunction "A1_6") (pintype "bidirectional"))
    )
    (net (code "88") (name "Net-(U12-A2)") (class "Default")
      (node (ref "JP5") (pin "2") (pinfunction "2_2") (pintype "passive"))
      (node (ref "U12") (pin "5") (pinfunction "A2_5") (pintype "bidirectional"))
    )
    (net (code "89") (name "Net-(U17-A12{slash}D+)") (class "Default")
      (node (ref "R53") (pin "2") (pinfunction "2_2") (pintype "passive"))
      (node (ref "U17") (pin "A12") (pinfunction "A12/D+_A12") (pintype "bidirectional"))
    )
    (net (code "90") (name "OA1+") (class "Default")
      (node (ref "D5") (pin "A") (pinfunction "ANODE_A") (pintype "passive"))
      (node (ref "R18") (pin "1") (pinfunction "1_1") (pintype "passive"))
      (node (ref "R82") (pin "1") (pinfunction "1_1") (pintype "passive"))
      (node (ref "R83") (pin "1") (pinfunction "1_1") (pintype "passive"))
    )
    (net (code "91") (name "OA1-") (class "Default")
      (node (ref "R20") (pin "1") (pinfunction "1_1") (pintype "passive"))
      (node (ref "R54") (pin "1") (pinfunction "1_1") (pintype "passive"))
      (node (ref "R55") (pin "1") (pinfunction "1_1") (pintype "passive"))
    )
    (net (code "92") (name "OA2+") (class "Default")
      (node (ref "D6") (pin "A") (pinfunction "ANODE_A") (pintype "passive"))
      (node (ref "R26") (pin "1") (pinfunction "1_1") (pintype "passive"))
      (node (ref "R86") (pin "1") (pinfunction "1_1") (pintype "passive"))
      (node (ref "R87") (pin "1") (pinfunction "1_1") (pintype "passive"))
    )
    (net (code "93") (name "OA2-") (class "Default")
      (node (ref "R28") (pin "1") (pinfunction "1_1") (pintype "passive"))
      (node (ref "R84") (pin "1") (pinfunction "1_1") (pintype "passive"))
      (node (ref "R85") (pin "1") (pinfunction "1_1") (pintype "passive"))
    )
    (net (code "94") (name "PA8") (class "Default")
      (node (ref "R42") (pin "2") (pinfunction "2_2") (pintype "passive"))
      (node (ref "R80") (pin "1") (pinfunction "1_1") (pintype "passive"))
      (node (ref "U17") (pin "A8") (pinfunction "A8_A8") (pintype "bidirectional"))
    )
    (net (code "95") (name "PA9") (class "Default")
      (node (ref "R4") (pin "1") (pinfunction "1_1") (pintype "passive"))
      (node (ref "R45") (pin "2") (pinfunction "2_2") (pintype "passive"))
      (node (ref "U17") (pin "A9") (pinfunction "A9_A9") (pintype "bidirectional"))
    )
    (net (code "96") (name "PA10") (class "Default")
      (node (ref "R46") (pin "2") (pinfunction "2_2") (pintype "passive"))
      (node (ref "R81") (pin "1") (pinfunction "1_1") (pintype "passive"))
      (node (ref "U17") (pin "A10") (pinfunction "A10_A10") (pintype "bidirectional"))
    )
    (net (code "97") (name "PB5") (class "Default")
      (node (ref "JP6") (pin "3") (pinfunction "3_3") (pintype "passive"))
      (node (ref "JP7") (pin "1") (pinfunction "1_1") (pintype "passive"))
      (node (ref "R49") (pin "1") (pinfunction "1_1") (pintype "passive"))
      (node (ref "U15") (pin "6") (pinfunction "SEL_6") (pintype "bidirectional"))
      (node (ref "U17") (pin "B5") (pinfunction "B5_B5") (pintype "bidirectional"))
    )
    (net (code "98") (name "PB8") (class "Default")
      (node (ref "R47") (pin "2") (pinfunction "2_2") (pintype "passive"))
      (node (ref "R6") (pin "1") (pinfunction "1_1") (pintype "passive"))
      (node (ref "U17") (pin "B8") (pinfunction "B8_B8") (pintype "bidirectional"))
    )
    (net (code "99") (name "PB12") (class "Default")
      (node (ref "R76") (pin "1") (pinfunction "1_1") (pintype "passive"))
      (node (ref "U17") (pin "B12") (pinfunction "B12_B12") (pintype "bidirectional"))
      (node (ref "U18") (pin "6") (pinfunction "SEL_6") (pintype "bidirectional"))
    )
    (net (code "100") (name "PGATE1") (class "Default")
      (node (ref "Q2") (pin "4") (pinfunction "G_4") (pintype "bidirectional"))
      (node (ref "R5") (pin "2") (pinfunction "2_2") (pintype "passive"))
      (node (ref "R88") (pin "1") (pinfunction "1_1") (pintype "passive"))
      (node (ref "U21") (pin "8") (pinfunction "DRVH_8") (pintype "bidirectional"))
    )
    (net (code "101") (name "PGATE2") (class "Default")
      (node (ref "Q3") (pin "4") (pinfunction "G_4") (pintype "bidirectional"))
      (node (ref "R58") (pin "1") (pinfunction "1_1") (pintype "passive"))
      (node (ref "R90") (pin "1") (pinfunction "1_1") (pintype "passive"))
      (node (ref "U3") (pin "8") (pinfunction "DRVH_8") (pintype "bidirectional"))
    )
    (net (code "102") (name "S1") (class "Default")
      (node (ref "S1") (pin "1") (pinfunction "1_1") (pintype "passive"))
      (node (ref "S1") (pin "2") (pinfunction "2_2") (pintype "passive"))
      (node (ref "U17") (pin "B9") (pinfunction "B9_B9") (pintype "bidirectional"))
    )
    (net (code "103") (name "S2") (class "Default")
      (node (ref "S2") (pin "1") (pinfunction "1_1") (pintype "passive"))
      (node (ref "S2") (pin "2") (pinfunction "2_2") (pintype "passive"))
      (node (ref "U17") (pin "C13") (pinfunction "C13_C13") (pintype "bidirectional"))
    )
    (net (code "104") (name "SCL-TX") (class "Default")
      (node (ref "JP1") (pin "2") (pinfunction "2_2") (pintype "passive"))
      (node (ref "JP2") (pin "2") (pinfunction "2_2") (pintype "passive"))
      (node (ref "LCD1") (pin "3=SCL") (pinfunction "SCL_3=SCL") (pintype "bidirectional"))
      (node (ref "U12") (pin "2") (pinfunction "SCL_2") (pintype "bidirectional"))
      (node (ref "U17") (pin "B10") (pinfunction "B10_B10") (pintype "bidirectional"))
    )
    (net (code "105") (name "SDA-RX") (class "Default")
      (node (ref "JP1") (pin "3") (pinfunction "3_3") (pintype "passive"))
      (node (ref "JP2") (pin "1") (pinfunction "1_1") (pintype "passive"))
      (node (ref "LCD1") (pin "4-SDA") (pinfunction "SDA_4-SDA") (pintype "bidirectional"))
      (node (ref "U12") (pin "1") (pinfunction "SDA_1") (pintype "bidirectional"))
      (node (ref "U17") (pin "B11") (pinfunction "B11_B11") (pintype "bidirectional"))
    )
    (net (code "106") (name "unconnected-(U12-OS-Pad3)") (class "Default")
      (node (ref "U12") (pin "3") (pinfunction "OS_3") (pintype "bidirectional"))
    )
    (net (code "107") (name "unconnected-(U17-PadRST)") (class "Default")
      (node (ref "U17") (pin "RST") (pinfunction "RST_RST") (pintype "bidirectional"))
    )
    (net (code "108") (name "unconnected-(U17-VB-PadVBAT)") (class "Default")
      (node (ref "U17") (pin "VBAT") (pinfunction "VB_VBAT") (pintype "bidirectional"))
    )
  )
)
